# single-spi-interface.net
KiCad netlist of a schematic drawn in EAGLE
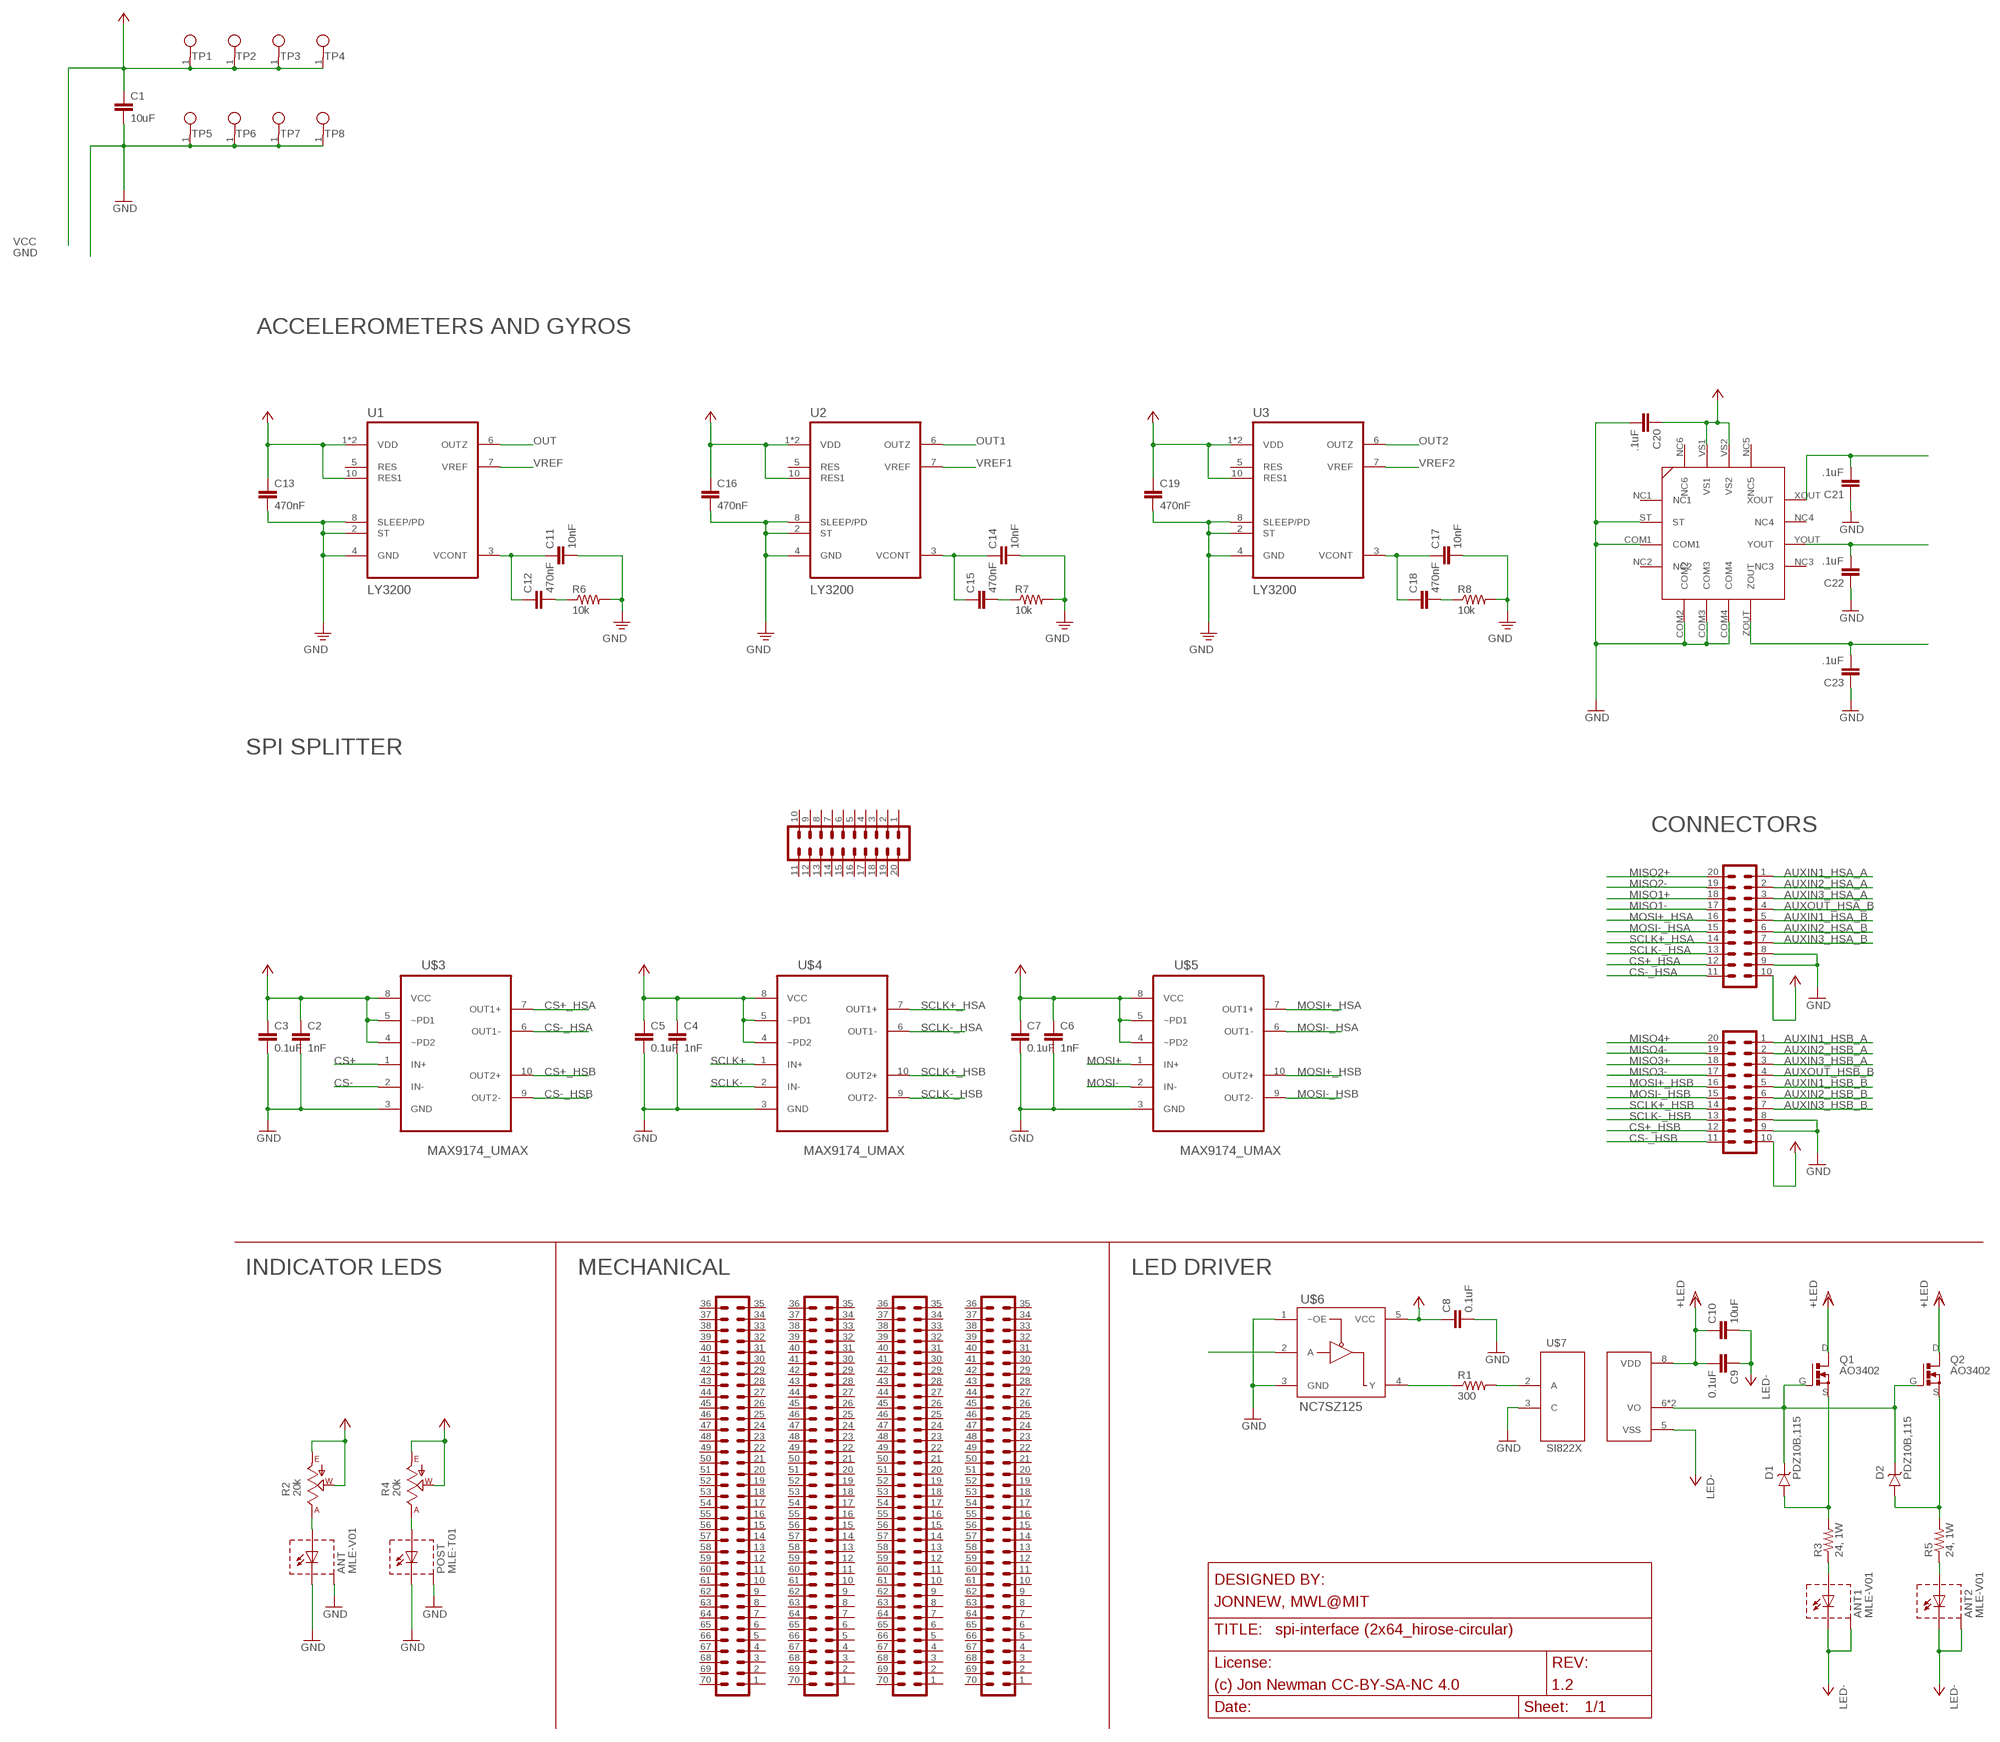
[diagram p0: schematic, sheet 1]

(export (version "E")
  (design (tool "Eeschema 10.0.6"))
  (components
    (comp (ref "ANT")
      (value "MLE-V01")
      (footprint "eagle-import:LED-MLE")
      (libsource (lib "eagle-import") (part "LED_PKG-BODY"))
    )
    (comp (ref "ANT1")
      (value "MLE-V01")
      (footprint "eagle-import:LED-MLE")
      (libsource (lib "eagle-import") (part "LED_PKG-BODY"))
    )
    (comp (ref "ANT2")
      (value "MLE-V01")
      (footprint "eagle-import:LED-MLE")
      (libsource (lib "eagle-import") (part "LED_PKG-BODY"))
    )
    (comp (ref "C1")
      (value "10uF")
      (footprint "eagle-import:0805")
      (fields (field (name "PARTNO") "C2012X5R1Cxxxxxxx"))
      (libsource (lib "eagle-import") (part "C_0805"))
    )
    (comp (ref "C2")
      (value "1nF")
      (footprint "eagle-import:0402")
      (libsource (lib "eagle-import") (part "jonnew_C_0402"))
    )
    (comp (ref "C3")
      (value "0.1uF")
      (footprint "eagle-import:0402")
      (libsource (lib "eagle-import") (part "jonnew_C_0402"))
    )
    (comp (ref "C4")
      (value "1nF")
      (footprint "eagle-import:0402")
      (libsource (lib "eagle-import") (part "jonnew_C_0402"))
    )
    (comp (ref "C5")
      (value "0.1uF")
      (footprint "eagle-import:0402")
      (libsource (lib "eagle-import") (part "jonnew_C_0402"))
    )
    (comp (ref "C6")
      (value "1nF")
      (footprint "eagle-import:0402")
      (libsource (lib "eagle-import") (part "jonnew_C_0402"))
    )
    (comp (ref "C7")
      (value "0.1uF")
      (footprint "eagle-import:0402")
      (libsource (lib "eagle-import") (part "jonnew_C_0402"))
    )
    (comp (ref "C8")
      (value "0.1uF")
      (footprint "eagle-import:0402")
      (libsource (lib "eagle-import") (part "jonnew_C_0402"))
    )
    (comp (ref "C9")
      (value "0.1uF")
      (footprint "eagle-import:0402")
      (libsource (lib "eagle-import") (part "jonnew_C_0402"))
    )
    (comp (ref "C10")
      (value "10uF")
      (footprint "eagle-import:0805")
      (fields (field (name "PARTNO") "C2012X5R1Cxxxxxxx"))
      (libsource (lib "eagle-import") (part "jonnew_C_0805"))
    )
    (comp (ref "C11")
      (value "10nF")
      (footprint "eagle-import:0201")
      (libsource (lib "eagle-import") (part "jonnew_C_0201"))
    )
    (comp (ref "C12")
      (value "470nF")
      (footprint "eagle-import:0201")
      (libsource (lib "eagle-import") (part "jonnew_C_0201"))
    )
    (comp (ref "C13")
      (value "470nF")
      (footprint "eagle-import:0201")
      (libsource (lib "eagle-import") (part "jonnew_C_0201"))
    )
    (comp (ref "C14")
      (value "10nF")
      (footprint "eagle-import:0201")
      (libsource (lib "eagle-import") (part "jonnew_C_0201"))
    )
    (comp (ref "C15")
      (value "470nF")
      (footprint "eagle-import:0201")
      (libsource (lib "eagle-import") (part "jonnew_C_0201"))
    )
    (comp (ref "C16")
      (value "470nF")
      (footprint "eagle-import:0201")
      (libsource (lib "eagle-import") (part "jonnew_C_0201"))
    )
    (comp (ref "C17")
      (value "10nF")
      (footprint "eagle-import:0201")
      (libsource (lib "eagle-import") (part "jonnew_C_0201"))
    )
    (comp (ref "C18")
      (value "470nF")
      (footprint "eagle-import:0201")
      (libsource (lib "eagle-import") (part "jonnew_C_0201"))
    )
    (comp (ref "C19")
      (value "470nF")
      (footprint "eagle-import:0201")
      (libsource (lib "eagle-import") (part "jonnew_C_0201"))
    )
    (comp (ref "C20")
      (value ".1uF")
      (footprint "eagle-import:0402")
      (libsource (lib "eagle-import") (part "C_0402"))
    )
    (comp (ref "C21")
      (value ".1uF")
      (footprint "eagle-import:0201")
      (libsource (lib "eagle-import") (part "jonnew_C_0201"))
    )
    (comp (ref "C22")
      (value ".1uF")
      (footprint "eagle-import:0201")
      (libsource (lib "eagle-import") (part "jonnew_C_0201"))
    )
    (comp (ref "C23")
      (value ".1uF")
      (footprint "eagle-import:0201")
      (libsource (lib "eagle-import") (part "jonnew_C_0201"))
    )
    (comp (ref "D1")
      (value "PDZ10B,115")
      (footprint "eagle-import:SOD-323")
      (libsource (lib "eagle-import") (part "Z-DIODE_SOD-323"))
    )
    (comp (ref "D2")
      (value "PDZ10B,115")
      (footprint "eagle-import:SOD-323")
      (libsource (lib "eagle-import") (part "Z-DIODE_SOD-323"))
    )
    (comp (ref "DIO_E1B")
      (value "PINHD-2X10_DF40-20REC")
      (footprint "eagle-import:DF40-20REC")
      (libsource (lib "eagle-import") (part "PINHD-2X10_DF40-20REC"))
    )
    (comp (ref "DIO_E1B1")
      (value "PINHD-2X10_DF40-20REC")
      (footprint "eagle-import:DF40-20REC")
      (libsource (lib "eagle-import") (part "PINHD-2X10_DF40-20REC"))
    )
    (comp (ref "MECH_E0B")
      (value "PINHD-2X35_DF40REC")
      (footprint "eagle-import:DF40-70REC")
      (libsource (lib "eagle-import") (part "PINHD-2X35_DF40REC"))
    )
    (comp (ref "MECH_N0B")
      (value "PINHD-2X35_DF40REC")
      (footprint "eagle-import:DF40-70REC")
      (libsource (lib "eagle-import") (part "PINHD-2X35_DF40REC"))
    )
    (comp (ref "MECH_S0B")
      (value "PINHD-2X35_DF40REC")
      (footprint "eagle-import:DF40-70REC")
      (libsource (lib "eagle-import") (part "PINHD-2X35_DF40REC"))
    )
    (comp (ref "MECH_W0B")
      (value "PINHD-2X35_DF40REC")
      (footprint "eagle-import:DF40-70REC")
      (libsource (lib "eagle-import") (part "PINHD-2X35_DF40REC"))
    )
    (comp (ref "POST")
      (value "MLE-T01")
      (footprint "eagle-import:LED-MLE")
      (libsource (lib "eagle-import") (part "LED_PKG-BODY"))
    )
    (comp (ref "Q1")
      (value "AO3402")
      (footprint "eagle-import:SOT23-GSD")
      (libsource (lib "eagle-import") (part "N-MOSFET_SOT23-GSD"))
    )
    (comp (ref "Q2")
      (value "AO3402")
      (footprint "eagle-import:SOT23-GSD")
      (libsource (lib "eagle-import") (part "N-MOSFET_SOT23-GSD"))
    )
    (comp (ref "R1")
      (value "300")
      (footprint "eagle-import:0402")
      (libsource (lib "eagle-import") (part "R_0402"))
    )
    (comp (ref "R2")
      (value "20k")
      (footprint "eagle-import:SM-42_43W")
      (libsource (lib "eagle-import") (part "TRIM_US-SM-42/43W"))
    )
    (comp (ref "R3")
      (value "24, 1W")
      (footprint "eagle-import:0402")
      (libsource (lib "eagle-import") (part "R_0402"))
    )
    (comp (ref "R4")
      (value "20k")
      (footprint "eagle-import:SM-42_43W")
      (libsource (lib "eagle-import") (part "TRIM_US-SM-42/43W"))
    )
    (comp (ref "R5")
      (value "24, 1W")
      (footprint "eagle-import:0402")
      (libsource (lib "eagle-import") (part "R_0402"))
    )
    (comp (ref "R6")
      (value "10k")
      (footprint "eagle-import:0201")
      (libsource (lib "eagle-import") (part "R_0201"))
    )
    (comp (ref "R7")
      (value "10k")
      (footprint "eagle-import:0201")
      (libsource (lib "eagle-import") (part "R_0201"))
    )
    (comp (ref "R8")
      (value "10k")
      (footprint "eagle-import:0201")
      (libsource (lib "eagle-import") (part "R_0201"))
    )
    (comp (ref "TP1")
      (value "TESTPOINT_SMALL")
      (footprint "eagle-import:TESTPOINT_SMALL")
      (libsource (lib "eagle-import") (part "TESTPOINT_SMALL"))
    )
    (comp (ref "TP2")
      (value "TESTPOINT_SMALL")
      (footprint "eagle-import:TESTPOINT_SMALL")
      (libsource (lib "eagle-import") (part "TESTPOINT_SMALL"))
    )
    (comp (ref "TP3")
      (value "TESTPOINT_SMALL")
      (footprint "eagle-import:TESTPOINT_SMALL")
      (libsource (lib "eagle-import") (part "TESTPOINT_SMALL"))
    )
    (comp (ref "TP4")
      (value "TESTPOINT_SMALL")
      (footprint "eagle-import:TESTPOINT_SMALL")
      (libsource (lib "eagle-import") (part "TESTPOINT_SMALL"))
    )
    (comp (ref "TP5")
      (value "TESTPOINT_SMALL")
      (footprint "eagle-import:TESTPOINT_SMALL")
      (libsource (lib "eagle-import") (part "TESTPOINT_SMALL"))
    )
    (comp (ref "TP6")
      (value "TESTPOINT_SMALL")
      (footprint "eagle-import:TESTPOINT_SMALL")
      (libsource (lib "eagle-import") (part "TESTPOINT_SMALL"))
    )
    (comp (ref "TP7")
      (value "TESTPOINT_SMALL")
      (footprint "eagle-import:TESTPOINT_SMALL")
      (libsource (lib "eagle-import") (part "TESTPOINT_SMALL"))
    )
    (comp (ref "TP8")
      (value "TESTPOINT_SMALL")
      (footprint "eagle-import:TESTPOINT_SMALL")
      (libsource (lib "eagle-import") (part "TESTPOINT_SMALL"))
    )
    (comp (ref "U$2")
      (value "PINHD-2X10_T1M")
      (footprint "eagle-import:T1M-10-T-DV")
      (libsource (lib "eagle-import") (part "PINHD-2X10_T1M"))
    )
    (comp (ref "U$3")
      (value "MAX9174_UMAX")
      (footprint "eagle-import:10-UMAX")
      (libsource (lib "eagle-import") (part "MAX9174_UMAX"))
    )
    (comp (ref "U$4")
      (value "MAX9174_UMAX")
      (footprint "eagle-import:10-UMAX")
      (libsource (lib "eagle-import") (part "MAX9174_UMAX"))
    )
    (comp (ref "U$5")
      (value "MAX9174_UMAX")
      (footprint "eagle-import:10-UMAX")
      (libsource (lib "eagle-import") (part "MAX9174_UMAX"))
    )
    (comp (ref "U$6")
      (value "NC7SZ125")
      (footprint "eagle-import:SOT-23-5")
      (libsource (lib "eagle-import") (part "NC7SZ125"))
    )
    (comp (ref "U$7")
      (value "SI822X")
      (footprint "eagle-import:SOIC127P500X400-8N")
      (libsource (lib "eagle-import") (part "SI822X"))
    )
    (comp (ref "U1")
      (value "LY3200")
      (footprint "eagle-import:LGA-10-COMPACT")
      (libsource (lib "eagle-import") (part "LY3200ALH_LGA-10-COMPACT"))
    )
    (comp (ref "U2")
      (value "LY3200")
      (footprint "eagle-import:LGA-10-COMPACT")
      (libsource (lib "eagle-import") (part "LY3200ALH_LGA-10-COMPACT"))
    )
    (comp (ref "U3")
      (value "LY3200")
      (footprint "eagle-import:LGA-10-COMPACT")
      (libsource (lib "eagle-import") (part "LY3200ALH_LGA-10-COMPACT"))
    )
    (comp (ref "U4")
      (value "ADXL335")
      (footprint "eagle-import:ADXL335")
      (libsource (lib "eagle-import") (part "ADXL335"))
    )
  )
  (nets
    (net (code "1") (name "+LED") (class "Default")
      (node (ref "C10") (pin "1") (pinfunction "1_1") (pintype "passive"))
      (node (ref "C9") (pin "2") (pinfunction "2_2") (pintype "passive"))
      (node (ref "Q1") (pin "D") (pinfunction "D_D") (pintype "bidirectional"))
      (node (ref "Q2") (pin "D") (pinfunction "D_D") (pintype "bidirectional"))
      (node (ref "U$7") (pin "8") (pinfunction "VDD_8") (pintype "power_in"))
    )
    (net (code "2") (name "/AUXIN1_HSA_A") (class "Default")
      (node (ref "DIO_E1B") (pin "1") (pinfunction "1_1") (pintype "bidirectional"))
    )
    (net (code "3") (name "/AUXIN1_HSA_B") (class "Default")
      (node (ref "DIO_E1B") (pin "5") (pinfunction "5_5") (pintype "bidirectional"))
    )
    (net (code "4") (name "/AUXIN1_HSB_A") (class "Default")
      (node (ref "DIO_E1B1") (pin "1") (pinfunction "1_1") (pintype "bidirectional"))
    )
    (net (code "5") (name "/AUXIN1_HSB_B") (class "Default")
      (node (ref "DIO_E1B1") (pin "5") (pinfunction "5_5") (pintype "bidirectional"))
    )
    (net (code "6") (name "/AUXIN2_HSA_A") (class "Default")
      (node (ref "DIO_E1B") (pin "2") (pinfunction "2_2") (pintype "bidirectional"))
    )
    (net (code "7") (name "/AUXIN2_HSA_B") (class "Default")
      (node (ref "DIO_E1B") (pin "6") (pinfunction "6_6") (pintype "bidirectional"))
    )
    (net (code "8") (name "/AUXIN2_HSB_A") (class "Default")
      (node (ref "DIO_E1B1") (pin "2") (pinfunction "2_2") (pintype "bidirectional"))
    )
    (net (code "9") (name "/AUXIN2_HSB_B") (class "Default")
      (node (ref "DIO_E1B1") (pin "6") (pinfunction "6_6") (pintype "bidirectional"))
    )
    (net (code "10") (name "/AUXIN3_HSA_A") (class "Default")
      (node (ref "DIO_E1B") (pin "3") (pinfunction "3_3") (pintype "bidirectional"))
    )
    (net (code "11") (name "/AUXIN3_HSA_B") (class "Default")
      (node (ref "DIO_E1B") (pin "7") (pinfunction "7_7") (pintype "bidirectional"))
    )
    (net (code "12") (name "/AUXIN3_HSB_A") (class "Default")
      (node (ref "DIO_E1B1") (pin "3") (pinfunction "3_3") (pintype "bidirectional"))
    )
    (net (code "13") (name "/AUXIN3_HSB_B") (class "Default")
      (node (ref "DIO_E1B1") (pin "7") (pinfunction "7_7") (pintype "bidirectional"))
    )
    (net (code "14") (name "/AUXOUT_HSA_B") (class "Default")
      (node (ref "DIO_E1B") (pin "4") (pinfunction "4_4") (pintype "bidirectional"))
    )
    (net (code "15") (name "/AUXOUT_HSB_B") (class "Default")
      (node (ref "DIO_E1B1") (pin "4") (pinfunction "4_4") (pintype "bidirectional"))
    )
    (net (code "16") (name "/CS+") (class "Default")
      (node (ref "U$3") (pin "1") (pinfunction "IN+_1") (pintype "input"))
    )
    (net (code "17") (name "/CS+_HSA") (class "Default")
      (node (ref "DIO_E1B") (pin "12") (pinfunction "12_12") (pintype "bidirectional"))
      (node (ref "U$3") (pin "7") (pinfunction "OUT1+_7") (pintype "output"))
    )
    (net (code "18") (name "/CS+_HSB") (class "Default")
      (node (ref "DIO_E1B1") (pin "12") (pinfunction "12_12") (pintype "bidirectional"))
      (node (ref "U$3") (pin "10") (pinfunction "OUT2+_10") (pintype "output"))
    )
    (net (code "19") (name "/CS-") (class "Default")
      (node (ref "U$3") (pin "2") (pinfunction "IN-_2") (pintype "input"))
    )
    (net (code "20") (name "/CS-_HSA") (class "Default")
      (node (ref "DIO_E1B") (pin "11") (pinfunction "11_11") (pintype "bidirectional"))
      (node (ref "U$3") (pin "6") (pinfunction "OUT1-_6") (pintype "output"))
    )
    (net (code "21") (name "/CS-_HSB") (class "Default")
      (node (ref "DIO_E1B1") (pin "11") (pinfunction "11_11") (pintype "bidirectional"))
      (node (ref "U$3") (pin "9") (pinfunction "OUT2-_9") (pintype "output"))
    )
    (net (code "22") (name "/MISO1+") (class "Default")
      (node (ref "DIO_E1B") (pin "18") (pinfunction "18_18") (pintype "bidirectional"))
    )
    (net (code "23") (name "/MISO1-") (class "Default")
      (node (ref "DIO_E1B") (pin "17") (pinfunction "17_17") (pintype "bidirectional"))
    )
    (net (code "24") (name "/MISO2+") (class "Default")
      (node (ref "DIO_E1B") (pin "20") (pinfunction "20_20") (pintype "bidirectional"))
    )
    (net (code "25") (name "/MISO2-") (class "Default")
      (node (ref "DIO_E1B") (pin "19") (pinfunction "19_19") (pintype "bidirectional"))
    )
    (net (code "26") (name "/MISO3+") (class "Default")
      (node (ref "DIO_E1B1") (pin "18") (pinfunction "18_18") (pintype "bidirectional"))
    )
    (net (code "27") (name "/MISO3-") (class "Default")
      (node (ref "DIO_E1B1") (pin "17") (pinfunction "17_17") (pintype "bidirectional"))
    )
    (net (code "28") (name "/MISO4+") (class "Default")
      (node (ref "DIO_E1B1") (pin "20") (pinfunction "20_20") (pintype "bidirectional"))
    )
    (net (code "29") (name "/MISO4-") (class "Default")
      (node (ref "DIO_E1B1") (pin "19") (pinfunction "19_19") (pintype "bidirectional"))
    )
    (net (code "30") (name "/MOSI+") (class "Default")
      (node (ref "U$5") (pin "1") (pinfunction "IN+_1") (pintype "input"))
    )
    (net (code "31") (name "/MOSI+_HSA") (class "Default")
      (node (ref "DIO_E1B") (pin "16") (pinfunction "16_16") (pintype "bidirectional"))
      (node (ref "U$5") (pin "7") (pinfunction "OUT1+_7") (pintype "output"))
    )
    (net (code "32") (name "/MOSI+_HSB") (class "Default")
      (node (ref "DIO_E1B1") (pin "16") (pinfunction "16_16") (pintype "bidirectional"))
      (node (ref "U$5") (pin "10") (pinfunction "OUT2+_10") (pintype "output"))
    )
    (net (code "33") (name "/MOSI-") (class "Default")
      (node (ref "U$5") (pin "2") (pinfunction "IN-_2") (pintype "input"))
    )
    (net (code "34") (name "/MOSI-_HSA") (class "Default")
      (node (ref "DIO_E1B") (pin "15") (pinfunction "15_15") (pintype "bidirectional"))
      (node (ref "U$5") (pin "6") (pinfunction "OUT1-_6") (pintype "output"))
    )
    (net (code "35") (name "/MOSI-_HSB") (class "Default")
      (node (ref "DIO_E1B1") (pin "15") (pinfunction "15_15") (pintype "bidirectional"))
      (node (ref "U$5") (pin "9") (pinfunction "OUT2-_9") (pintype "output"))
    )
    (net (code "36") (name "/OUT") (class "Default")
      (node (ref "U1") (pin "6") (pinfunction "OUTZ_6") (pintype "output"))
    )
    (net (code "37") (name "/OUT1") (class "Default")
      (node (ref "U2") (pin "6") (pinfunction "OUTZ_6") (pintype "output"))
    )
    (net (code "38") (name "/OUT2") (class "Default")
      (node (ref "U3") (pin "6") (pinfunction "OUTZ_6") (pintype "output"))
    )
    (net (code "39") (name "/SCLK+") (class "Default")
      (node (ref "U$4") (pin "1") (pinfunction "IN+_1") (pintype "input"))
    )
    (net (code "40") (name "/SCLK+_HSA") (class "Default")
      (node (ref "DIO_E1B") (pin "14") (pinfunction "14_14") (pintype "bidirectional"))
      (node (ref "U$4") (pin "7") (pinfunction "OUT1+_7") (pintype "output"))
    )
    (net (code "41") (name "/SCLK+_HSB") (class "Default")
      (node (ref "DIO_E1B1") (pin "14") (pinfunction "14_14") (pintype "bidirectional"))
      (node (ref "U$4") (pin "10") (pinfunction "OUT2+_10") (pintype "output"))
    )
    (net (code "42") (name "/SCLK-") (class "Default")
      (node (ref "U$4") (pin "2") (pinfunction "IN-_2") (pintype "input"))
    )
    (net (code "43") (name "/SCLK-_HSA") (class "Default")
      (node (ref "DIO_E1B") (pin "13") (pinfunction "13_13") (pintype "bidirectional"))
      (node (ref "U$4") (pin "6") (pinfunction "OUT1-_6") (pintype "output"))
    )
    (net (code "44") (name "/SCLK-_HSB") (class "Default")
      (node (ref "DIO_E1B1") (pin "13") (pinfunction "13_13") (pintype "bidirectional"))
      (node (ref "U$4") (pin "9") (pinfunction "OUT2-_9") (pintype "output"))
    )
    (net (code "45") (name "/VREF") (class "Default")
      (node (ref "U1") (pin "7") (pinfunction "VREF_7") (pintype "output"))
    )
    (net (code "46") (name "/VREF1") (class "Default")
      (node (ref "U2") (pin "7") (pinfunction "VREF_7") (pintype "output"))
    )
    (net (code "47") (name "/VREF2") (class "Default")
      (node (ref "U3") (pin "7") (pinfunction "VREF_7") (pintype "output"))
    )
    (net (code "48") (name "GND") (class "Default")
      (node (ref "ANT") (pin "C1") (pinfunction "C_C1") (pintype "passive"))
      (node (ref "ANT") (pin "C2") (pinfunction "C_C2") (pintype "passive"))
      (node (ref "ANT") (pin "HS") (pinfunction "BODY_HS") (pintype "passive"))
      (node (ref "C1") (pin "2") (pinfunction "2_2") (pintype "passive"))
      (node (ref "C11") (pin "2") (pinfunction "2_2") (pintype "passive"))
      (node (ref "C13") (pin "2") (pinfunction "2_2") (pintype "passive"))
      (node (ref "C14") (pin "2") (pinfunction "2_2") (pintype "passive"))
      (node (ref "C16") (pin "2") (pinfunction "2_2") (pintype "passive"))
      (node (ref "C17") (pin "2") (pinfunction "2_2") (pintype "passive"))
      (node (ref "C19") (pin "2") (pinfunction "2_2") (pintype "passive"))
      (node (ref "C2") (pin "2") (pinfunction "2_2") (pintype "passive"))
      (node (ref "C20") (pin "2") (pinfunction "2_2") (pintype "passive"))
      (node (ref "C21") (pin "1") (pinfunction "1_1") (pintype "passive"))
      (node (ref "C22") (pin "1") (pinfunction "1_1") (pintype "passive"))
      (node (ref "C23") (pin "1") (pinfunction "1_1") (pintype "passive"))
      (node (ref "C3") (pin "2") (pinfunction "2_2") (pintype "passive"))
      (node (ref "C4") (pin "2") (pinfunction "2_2") (pintype "passive"))
      (node (ref "C5") (pin "2") (pinfunction "2_2") (pintype "passive"))
      (node (ref "C6") (pin "2") (pinfunction "2_2") (pintype "passive"))
      (node (ref "C7") (pin "2") (pinfunction "2_2") (pintype "passive"))
      (node (ref "C8") (pin "2") (pinfunction "2_2") (pintype "passive"))
      (node (ref "DIO_E1B") (pin "8") (pinfunction "8_8") (pintype "bidirectional"))
      (node (ref "DIO_E1B") (pin "9") (pinfunction "9_9") (pintype "bidirectional"))
      (node (ref "DIO_E1B1") (pin "8") (pinfunction "8_8") (pintype "bidirectional"))
      (node (ref "DIO_E1B1") (pin "9") (pinfunction "9_9") (pintype "bidirectional"))
      (node (ref "POST") (pin "C1") (pinfunction "C_C1") (pintype "passive"))
      (node (ref "POST") (pin "C2") (pinfunction "C_C2") (pintype "passive"))
      (node (ref "POST") (pin "HS") (pinfunction "BODY_HS") (pintype "passive"))
      (node (ref "R6") (pin "2") (pinfunction "2_2") (pintype "passive"))
      (node (ref "R7") (pin "2") (pinfunction "2_2") (pintype "passive"))
      (node (ref "R8") (pin "2") (pinfunction "2_2") (pintype "passive"))
      (node (ref "TP5") (pin "1") (pinfunction "1_1") (pintype "passive"))
      (node (ref "TP6") (pin "1") (pinfunction "1_1") (pintype "passive"))
      (node (ref "TP7") (pin "1") (pinfunction "1_1") (pintype "passive"))
      (node (ref "TP8") (pin "1") (pinfunction "1_1") (pintype "passive"))
      (node (ref "U$3") (pin "3") (pinfunction "GND_3") (pintype "power_in"))
      (node (ref "U$4") (pin "3") (pinfunction "GND_3") (pintype "power_in"))
      (node (ref "U$5") (pin "3") (pinfunction "GND_3") (pintype "power_in"))
      (node (ref "U$6") (pin "1") (pinfunction "~{OE}_1") (pintype "input"))
      (node (ref "U$6") (pin "3") (pinfunction "GND_3") (pintype "power_in"))
      (node (ref "U$7") (pin "3") (pinfunction "C_3") (pintype "bidirectional"))
      (node (ref "U1") (pin "2") (pinfunction "ST_2") (pintype "bidirectional"))
      (node (ref "U1") (pin "4") (pinfunction "GND_4") (pintype "power_in"))
      (node (ref "U1") (pin "8") (pinfunction "SLEEP/PD_8") (pintype "bidirectional"))
      (node (ref "U2") (pin "2") (pinfunction "ST_2") (pintype "bidirectional"))
      (node (ref "U2") (pin "4") (pinfunction "GND_4") (pintype "power_in"))
      (node (ref "U2") (pin "8") (pinfunction "SLEEP/PD_8") (pintype "bidirectional"))
      (node (ref "U3") (pin "2") (pinfunction "ST_2") (pintype "bidirectional"))
      (node (ref "U3") (pin "4") (pinfunction "GND_4") (pintype "power_in"))
      (node (ref "U3") (pin "8") (pinfunction "SLEEP/PD_8") (pintype "bidirectional"))
      (node (ref "U4") (pin "COM1") (pinfunction "COM1_COM1") (pintype "bidirectional"))
      (node (ref "U4") (pin "COM2") (pinfunction "COM2_COM2") (pintype "bidirectional"))
      (node (ref "U4") (pin "COM3") (pinfunction "COM3_COM3") (pintype "bidirectional"))
      (node (ref "U4") (pin "COM4") (pinfunction "COM4_COM4") (pintype "bidirectional"))
      (node (ref "U4") (pin "ST") (pinfunction "ST_ST") (pintype "bidirectional"))
    )
    (net (code "49") (name "LED-") (class "Default")
      (node (ref "ANT1") (pin "C1") (pinfunction "C_C1") (pintype "passive"))
      (node (ref "ANT1") (pin "C2") (pinfunction "C_C2") (pintype "passive"))
      (node (ref "ANT1") (pin "HS") (pinfunction "BODY_HS") (pintype "passive"))
      (node (ref "ANT2") (pin "C1") (pinfunction "C_C1") (pintype "passive"))
      (node (ref "ANT2") (pin "C2") (pinfunction "C_C2") (pintype "passive"))
      (node (ref "ANT2") (pin "HS") (pinfunction "BODY_HS") (pintype "passive"))
      (node (ref "C10") (pin "2") (pinfunction "2_2") (pintype "passive"))
      (node (ref "C9") (pin "1") (pinfunction "1_1") (pintype "passive"))
      (node (ref "U$7") (pin "5") (pinfunction "VSS_5") (pintype "power_in"))
    )
    (net (code "50") (name "Net-(ANT1-A-PadA1)") (class "Default")
      (node (ref "ANT1") (pin "A1") (pinfunction "A_A1") (pintype "passive"))
      (node (ref "ANT1") (pin "A2") (pinfunction "A_A2") (pintype "passive"))
      (node (ref "R3") (pin "1") (pinfunction "1_1") (pintype "passive"))
    )
    (net (code "51") (name "Net-(ANT2-A-PadA1)") (class "Default")
      (node (ref "ANT2") (pin "A1") (pinfunction "A_A1") (pintype "passive"))
      (node (ref "ANT2") (pin "A2") (pinfunction "A_A2") (pintype "passive"))
      (node (ref "R5") (pin "1") (pinfunction "1_1") (pintype "passive"))
    )
    (net (code "52") (name "Net-(C12-Pad2)") (class "Default")
      (node (ref "C12") (pin "2") (pinfunction "2_2") (pintype "passive"))
      (node (ref "R6") (pin "1") (pinfunction "1_1") (pintype "passive"))
    )
    (net (code "53") (name "Net-(C15-Pad2)") (class "Default")
      (node (ref "C15") (pin "2") (pinfunction "2_2") (pintype "passive"))
      (node (ref "R7") (pin "1") (pinfunction "1_1") (pintype "passive"))
    )
    (net (code "54") (name "Net-(C18-Pad2)") (class "Default")
      (node (ref "C18") (pin "2") (pinfunction "2_2") (pintype "passive"))
      (node (ref "R8") (pin "1") (pinfunction "1_1") (pintype "passive"))
    )
    (net (code "55") (name "Net-(C21-Pad2)") (class "Default")
      (node (ref "C21") (pin "2") (pinfunction "2_2") (pintype "passive"))
      (node (ref "U4") (pin "XOUT") (pinfunction "XOUT_XOUT") (pintype "bidirectional"))
    )
    (net (code "56") (name "Net-(C22-Pad2)") (class "Default")
      (node (ref "C22") (pin "2") (pinfunction "2_2") (pintype "passive"))
      (node (ref "U4") (pin "YOUT") (pinfunction "YOUT_YOUT") (pintype "bidirectional"))
    )
    (net (code "57") (name "Net-(C23-Pad2)") (class "Default")
      (node (ref "C23") (pin "2") (pinfunction "2_2") (pintype "passive"))
      (node (ref "U4") (pin "ZOUT") (pinfunction "ZOUT_ZOUT") (pintype "bidirectional"))
    )
    (net (code "58") (name "Net-(D1-PadA)") (class "Default")
      (node (ref "D1") (pin "A") (pinfunction "A_A") (pintype "passive"))
      (node (ref "Q1") (pin "S") (pinfunction "S_S") (pintype "bidirectional"))
      (node (ref "R3") (pin "2") (pinfunction "2_2") (pintype "passive"))
    )
    (net (code "59") (name "Net-(D1-PadC)") (class "Default")
      (node (ref "D1") (pin "C") (pinfunction "C_C") (pintype "passive"))
      (node (ref "D2") (pin "C") (pinfunction "C_C") (pintype "passive"))
      (node (ref "Q1") (pin "G") (pinfunction "G_G") (pintype "bidirectional"))
      (node (ref "Q2") (pin "G") (pinfunction "G_G") (pintype "bidirectional"))
      (node (ref "U$7") (pin "6") (pinfunction "VO_6") (pintype "bidirectional"))
      (node (ref "U$7") (pin "7") (pinfunction "VO_7") (pintype "bidirectional"))
    )
    (net (code "60") (name "Net-(D2-PadA)") (class "Default")
      (node (ref "D2") (pin "A") (pinfunction "A_A") (pintype "passive"))
      (node (ref "Q2") (pin "S") (pinfunction "S_S") (pintype "bidirectional"))
      (node (ref "R5") (pin "2") (pinfunction "2_2") (pintype "passive"))
    )
    (net (code "61") (name "Net-(R2-A)") (class "Default")
      (node (ref "ANT") (pin "A1") (pinfunction "A_A1") (pintype "passive"))
      (node (ref "ANT") (pin "A2") (pinfunction "A_A2") (pintype "passive"))
      (node (ref "R2") (pin "1") (pinfunction "A_1") (pintype "passive"))
    )
    (net (code "62") (name "Net-(R4-A)") (class "Default")
      (node (ref "POST") (pin "A1") (pinfunction "A_A1") (pintype "passive"))
      (node (ref "POST") (pin "A2") (pinfunction "A_A2") (pintype "passive"))
      (node (ref "R4") (pin "1") (pinfunction "A_1") (pintype "passive"))
    )
    (net (code "63") (name "Net-(U$6-Y)") (class "Default")
      (node (ref "R1") (pin "1") (pinfunction "1_1") (pintype "passive"))
      (node (ref "U$6") (pin "4") (pinfunction "Y_4") (pintype "output"))
    )
    (net (code "64") (name "Net-(U$7-A)") (class "Default")
      (node (ref "R1") (pin "2") (pinfunction "2_2") (pintype "passive"))
      (node (ref "U$7") (pin "2") (pinfunction "A_2") (pintype "bidirectional"))
    )
    (net (code "65") (name "Net-(U1-VCONT)") (class "Default")
      (node (ref "C11") (pin "1") (pinfunction "1_1") (pintype "passive"))
      (node (ref "C12") (pin "1") (pinfunction "1_1") (pintype "passive"))
      (node (ref "U1") (pin "3") (pinfunction "VCONT_3") (pintype "passive"))
    )
    (net (code "66") (name "Net-(U2-VCONT)") (class "Default")
      (node (ref "C14") (pin "1") (pinfunction "1_1") (pintype "passive"))
      (node (ref "C15") (pin "1") (pinfunction "1_1") (pintype "passive"))
      (node (ref "U2") (pin "3") (pinfunction "VCONT_3") (pintype "passive"))
    )
    (net (code "67") (name "Net-(U3-VCONT)") (class "Default")
      (node (ref "C17") (pin "1") (pinfunction "1_1") (pintype "passive"))
      (node (ref "C18") (pin "1") (pinfunction "1_1") (pintype "passive"))
      (node (ref "U3") (pin "3") (pinfunction "VCONT_3") (pintype "passive"))
    )
    (net (code "68") (name "VCC") (class "Default")
      (node (ref "C1") (pin "1") (pinfunction "1_1") (pintype "passive"))
      (node (ref "C13") (pin "1") (pinfunction "1_1") (pintype "passive"))
      (node (ref "C16") (pin "1") (pinfunction "1_1") (pintype "passive"))
      (node (ref "C19") (pin "1") (pinfunction "1_1") (pintype "passive"))
      (node (ref "C2") (pin "1") (pinfunction "1_1") (pintype "passive"))
      (node (ref "C20") (pin "1") (pinfunction "1_1") (pintype "passive"))
      (node (ref "C3") (pin "1") (pinfunction "1_1") (pintype "passive"))
      (node (ref "C4") (pin "1") (pinfunction "1_1") (pintype "passive"))
      (node (ref "C5") (pin "1") (pinfunction "1_1") (pintype "passive"))
      (node (ref "C6") (pin "1") (pinfunction "1_1") (pintype "passive"))
      (node (ref "C7") (pin "1") (pinfunction "1_1") (pintype "passive"))
      (node (ref "C8") (pin "1") (pinfunction "1_1") (pintype "passive"))
      (node (ref "DIO_E1B") (pin "10") (pinfunction "10_10") (pintype "bidirectional"))
      (node (ref "DIO_E1B1") (pin "10") (pinfunction "10_10") (pintype "bidirectional"))
      (node (ref "R2") (pin "2") (pinfunction "W_2") (pintype "passive"))
      (node (ref "R2") (pin "3") (pinfunction "E_3") (pintype "passive"))
      (node (ref "R4") (pin "2") (pinfunction "W_2") (pintype "passive"))
      (node (ref "R4") (pin "3") (pinfunction "E_3") (pintype "passive"))
      (node (ref "TP1") (pin "1") (pinfunction "1_1") (pintype "passive"))
      (node (ref "TP2") (pin "1") (pinfunction "1_1") (pintype "passive"))
      (node (ref "TP3") (pin "1") (pinfunction "1_1") (pintype "passive"))
      (node (ref "TP4") (pin "1") (pinfunction "1_1") (pintype "passive"))
      (node (ref "U$3") (pin "4") (pinfunction "~{PD2}_4") (pintype "passive"))
      (node (ref "U$3") (pin "5") (pinfunction "~{PD1}_5") (pintype "passive"))
      (node (ref "U$3") (pin "8") (pinfunction "VCC_8") (pintype "power_in"))
      (node (ref "U$4") (pin "4") (pinfunction "~{PD2}_4") (pintype "passive"))
      (node (ref "U$4") (pin "5") (pinfunction "~{PD1}_5") (pintype "passive"))
      (node (ref "U$4") (pin "8") (pinfunction "VCC_8") (pintype "power_in"))
      (node (ref "U$5") (pin "4") (pinfunction "~{PD2}_4") (pintype "passive"))
      (node (ref "U$5") (pin "5") (pinfunction "~{PD1}_5") (pintype "passive"))
      (node (ref "U$5") (pin "8") (pinfunction "VCC_8") (pintype "power_in"))
      (node (ref "U$6") (pin "5") (pinfunction "VCC_5") (pintype "power_in"))
      (node (ref "U1") (pin "1") (pinfunction "VDD_1") (pintype "power_in"))
      (node (ref "U1") (pin "10") (pinfunction "RES1_10") (pintype "passive"))
      (node (ref "U1") (pin "9") (pinfunction "VDD_9") (pintype "power_in"))
      (node (ref "U2") (pin "1") (pinfunction "VDD_1") (pintype "power_in"))
      (node (ref "U2") (pin "10") (pinfunction "RES1_10") (pintype "passive"))
      (node (ref "U2") (pin "9") (pinfunction "VDD_9") (pintype "power_in"))
      (node (ref "U3") (pin "1") (pinfunction "VDD_1") (pintype "power_in"))
      (node (ref "U3") (pin "10") (pinfunction "RES1_10") (pintype "passive"))
      (node (ref "U3") (pin "9") (pinfunction "VDD_9") (pintype "power_in"))
      (node (ref "U4") (pin "VS1") (pinfunction "VS1_VS1") (pintype "bidirectional"))
      (node (ref "U4") (pin "VS2") (pinfunction "VS2_VS2") (pintype "bidirectional"))
    )
    (net (code "69") (name "unconnected-(MECH_E0B-Pad1)") (class "Default")
      (node (ref "MECH_E0B") (pin "1") (pinfunction "1_1") (pintype "bidirectional"))
    )
    (net (code "70") (name "unconnected-(MECH_E0B-Pad2)") (class "Default")
      (node (ref "MECH_E0B") (pin "2") (pinfunction "2_2") (pintype "bidirectional"))
    )
    (net (code "71") (name "unconnected-(MECH_E0B-Pad3)") (class "Default")
      (node (ref "MECH_E0B") (pin "3") (pinfunction "3_3") (pintype "bidirectional"))
    )
    (net (code "72") (name "unconnected-(MECH_E0B-Pad4)") (class "Default")
      (node (ref "MECH_E0B") (pin "4") (pinfunction "4_4") (pintype "bidirectional"))
    )
    (net (code "73") (name "unconnected-(MECH_E0B-Pad5)") (class "Default")
      (node (ref "MECH_E0B") (pin "5") (pinfunction "5_5") (pintype "bidirectional"))
    )
    (net (code "74") (name "unconnected-(MECH_E0B-Pad6)") (class "Default")
      (node (ref "MECH_E0B") (pin "6") (pinfunction "6_6") (pintype "bidirectional"))
    )
    (net (code "75") (name "unconnected-(MECH_E0B-Pad7)") (class "Default")
      (node (ref "MECH_E0B") (pin "7") (pinfunction "7_7") (pintype "bidirectional"))
    )
    (net (code "76") (name "unconnected-(MECH_E0B-Pad8)") (class "Default")
      (node (ref "MECH_E0B") (pin "8") (pinfunction "8_8") (pintype "bidirectional"))
    )
    (net (code "77") (name "unconnected-(MECH_E0B-Pad9)") (class "Default")
      (node (ref "MECH_E0B") (pin "9") (pinfunction "9_9") (pintype "bidirectional"))
    )
    (net (code "78") (name "unconnected-(MECH_E0B-Pad10)") (class "Default")
      (node (ref "MECH_E0B") (pin "10") (pinfunction "10_10") (pintype "bidirectional"))
    )
    (net (code "79") (name "unconnected-(MECH_E0B-Pad11)") (class "Default")
      (node (ref "MECH_E0B") (pin "11") (pinfunction "11_11") (pintype "bidirectional"))
    )
    (net (code "80") (name "unconnected-(MECH_E0B-Pad12)") (class "Default")
      (node (ref "MECH_E0B") (pin "12") (pinfunction "12_12") (pintype "bidirectional"))
    )
    (net (code "81") (name "unconnected-(MECH_E0B-Pad13)") (class "Default")
      (node (ref "MECH_E0B") (pin "13") (pinfunction "13_13") (pintype "bidirectional"))
    )
    (net (code "82") (name "unconnected-(MECH_E0B-Pad14)") (class "Default")
      (node (ref "MECH_E0B") (pin "14") (pinfunction "14_14") (pintype "bidirectional"))
    )
    (net (code "83") (name "unconnected-(MECH_E0B-Pad15)") (class "Default")
      (node (ref "MECH_E0B") (pin "15") (pinfunction "15_15") (pintype "bidirectional"))
    )
    (net (code "84") (name "unconnected-(MECH_E0B-Pad16)") (class "Default")
      (node (ref "MECH_E0B") (pin "16") (pinfunction "16_16") (pintype "bidirectional"))
    )
    (net (code "85") (name "unconnected-(MECH_E0B-Pad17)") (class "Default")
      (node (ref "MECH_E0B") (pin "17") (pinfunction "17_17") (pintype "bidirectional"))
    )
    (net (code "86") (name "unconnected-(MECH_E0B-Pad18)") (class "Default")
      (node (ref "MECH_E0B") (pin "18") (pinfunction "18_18") (pintype "bidirectional"))
    )
    (net (code "87") (name "unconnected-(MECH_E0B-Pad19)") (class "Default")
      (node (ref "MECH_E0B") (pin "19") (pinfunction "19_19") (pintype "bidirectional"))
    )
    (net (code "88") (name "unconnected-(MECH_E0B-Pad20)") (class "Default")
      (node (ref "MECH_E0B") (pin "20") (pinfunction "20_20") (pintype "bidirectional"))
    )
    (net (code "89") (name "unconnected-(MECH_E0B-Pad21)") (class "Default")
      (node (ref "MECH_E0B") (pin "21") (pinfunction "21_21") (pintype "bidirectional"))
    )
    (net (code "90") (name "unconnected-(MECH_E0B-Pad22)") (class "Default")
      (node (ref "MECH_E0B") (pin "22") (pinfunction "22_22") (pintype "bidirectional"))
    )
    (net (code "91") (name "unconnected-(MECH_E0B-Pad23)") (class "Default")
      (node (ref "MECH_E0B") (pin "23") (pinfunction "23_23") (pintype "bidirectional"))
    )
    (net (code "92") (name "unconnected-(MECH_E0B-Pad24)") (class "Default")
      (node (ref "MECH_E0B") (pin "24") (pinfunction "24_24") (pintype "bidirectional"))
    )
    (net (code "93") (name "unconnected-(MECH_E0B-Pad25)") (class "Default")
      (node (ref "MECH_E0B") (pin "25") (pinfunction "25_25") (pintype "bidirectional"))
    )
    (net (code "94") (name "unconnected-(MECH_E0B-Pad26)") (class "Default")
      (node (ref "MECH_E0B") (pin "26") (pinfunction "26_26") (pintype "bidirectional"))
    )
    (net (code "95") (name "unconnected-(MECH_E0B-Pad27)") (class "Default")
      (node (ref "MECH_E0B") (pin "27") (pinfunction "27_27") (pintype "bidirectional"))
    )
    (net (code "96") (name "unconnected-(MECH_E0B-Pad28)") (class "Default")
      (node (ref "MECH_E0B") (pin "28") (pinfunction "28_28") (pintype "bidirectional"))
    )
    (net (code "97") (name "unconnected-(MECH_E0B-Pad29)") (class "Default")
      (node (ref "MECH_E0B") (pin "29") (pinfunction "29_29") (pintype "bidirectional"))
    )
    (net (code "98") (name "unconnected-(MECH_E0B-Pad30)") (class "Default")
      (node (ref "MECH_E0B") (pin "30") (pinfunction "30_30") (pintype "bidirectional"))
    )
    (net (code "99") (name "unconnected-(MECH_E0B-Pad31)") (class "Default")
      (node (ref "MECH_E0B") (pin "31") (pinfunction "31_31") (pintype "bidirectional"))
    )
    (net (code "100") (name "unconnected-(MECH_E0B-Pad32)") (class "Default")
      (node (ref "MECH_E0B") (pin "32") (pinfunction "32_32") (pintype "bidirectional"))
    )
    (net (code "101") (name "unconnected-(MECH_E0B-Pad33)") (class "Default")
      (node (ref "MECH_E0B") (pin "33") (pinfunction "33_33") (pintype "bidirectional"))
    )
    (net (code "102") (name "unconnected-(MECH_E0B-Pad34)") (class "Default")
      (node (ref "MECH_E0B") (pin "34") (pinfunction "34_34") (pintype "bidirectional"))
    )
    (net (code "103") (name "unconnected-(MECH_E0B-Pad35)") (class "Default")
      (node (ref "MECH_E0B") (pin "35") (pinfunction "35_35") (pintype "bidirectional"))
    )
    (net (code "104") (name "unconnected-(MECH_E0B-Pad36)") (class "Default")
      (node (ref "MECH_E0B") (pin "36") (pinfunction "36_36") (pintype "bidirectional"))
    )
    (net (code "105") (name "unconnected-(MECH_E0B-Pad37)") (class "Default")
      (node (ref "MECH_E0B") (pin "37") (pinfunction "37_37") (pintype "bidirectional"))
    )
    (net (code "106") (name "unconnected-(MECH_E0B-Pad38)") (class "Default")
      (node (ref "MECH_E0B") (pin "38") (pinfunction "38_38") (pintype "bidirectional"))
    )
    (net (code "107") (name "unconnected-(MECH_E0B-Pad39)") (class "Default")
      (node (ref "MECH_E0B") (pin "39") (pinfunction "39_39") (pintype "bidirectional"))
    )
    (net (code "108") (name "unconnected-(MECH_E0B-Pad40)") (class "Default")
      (node (ref "MECH_E0B") (pin "40") (pinfunction "40_40") (pintype "bidirectional"))
    )
    (net (code "109") (name "unconnected-(MECH_E0B-Pad41)") (class "Default")
      (node (ref "MECH_E0B") (pin "41") (pinfunction "41_41") (pintype "bidirectional"))
    )
    (net (code "110") (name "unconnected-(MECH_E0B-Pad42)") (class "Default")
      (node (ref "MECH_E0B") (pin "42") (pinfunction "42_42") (pintype "bidirectional"))
    )
    (net (code "111") (name "unconnected-(MECH_E0B-Pad43)") (class "Default")
      (node (ref "MECH_E0B") (pin "43") (pinfunction "43_43") (pintype "bidirectional"))
    )
    (net (code "112") (name "unconnected-(MECH_E0B-Pad44)") (class "Default")
      (node (ref "MECH_E0B") (pin "44") (pinfunction "44_44") (pintype "bidirectional"))
    )
    (net (code "113") (name "unconnected-(MECH_E0B-Pad45)") (class "Default")
      (node (ref "MECH_E0B") (pin "45") (pinfunction "45_45") (pintype "bidirectional"))
    )
    (net (code "114") (name "unconnected-(MECH_E0B-Pad46)") (class "Default")
      (node (ref "MECH_E0B") (pin "46") (pinfunction "46_46") (pintype "bidirectional"))
    )
    (net (code "115") (name "unconnected-(MECH_E0B-Pad47)") (class "Default")
      (node (ref "MECH_E0B") (pin "47") (pinfunction "47_47") (pintype "bidirectional"))
    )
    (net (code "116") (name "unconnected-(MECH_E0B-Pad48)") (class "Default")
      (node (ref "MECH_E0B") (pin "48") (pinfunction "48_48") (pintype "bidirectional"))
    )
    (net (code "117") (name "unconnected-(MECH_E0B-Pad49)") (class "Default")
      (node (ref "MECH_E0B") (pin "49") (pinfunction "49_49") (pintype "bidirectional"))
    )
    (net (code "118") (name "unconnected-(MECH_E0B-Pad50)") (class "Default")
      (node (ref "MECH_E0B") (pin "50") (pinfunction "50_50") (pintype "bidirectional"))
    )
    (net (code "119") (name "unconnected-(MECH_E0B-Pad51)") (class "Default")
      (node (ref "MECH_E0B") (pin "51") (pinfunction "51_51") (pintype "bidirectional"))
    )
    (net (code "120") (name "unconnected-(MECH_E0B-Pad52)") (class "Default")
      (node (ref "MECH_E0B") (pin "52") (pinfunction "52_52") (pintype "bidirectional"))
    )
    (net (code "121") (name "unconnected-(MECH_E0B-Pad53)") (class "Default")
      (node (ref "MECH_E0B") (pin "53") (pinfunction "53_53") (pintype "bidirectional"))
    )
    (net (code "122") (name "unconnected-(MECH_E0B-Pad54)") (class "Default")
      (node (ref "MECH_E0B") (pin "54") (pinfunction "54_54") (pintype "bidirectional"))
    )
    (net (code "123") (name "unconnected-(MECH_E0B-Pad55)") (class "Default")
      (node (ref "MECH_E0B") (pin "55") (pinfunction "55_55") (pintype "bidirectional"))
    )
    (net (code "124") (name "unconnected-(MECH_E0B-Pad56)") (class "Default")
      (node (ref "MECH_E0B") (pin "56") (pinfunction "56_56") (pintype "bidirectional"))
    )
    (net (code "125") (name "unconnected-(MECH_E0B-Pad57)") (class "Default")
      (node (ref "MECH_E0B") (pin "57") (pinfunction "57_57") (pintype "bidirectional"))
    )
    (net (code "126") (name "unconnected-(MECH_E0B-Pad58)") (class "Default")
      (node (ref "MECH_E0B") (pin "58") (pinfunction "58_58") (pintype "bidirectional"))
    )
    (net (code "127") (name "unconnected-(MECH_E0B-Pad59)") (class "Default")
      (node (ref "MECH_E0B") (pin "59") (pinfunction "59_59") (pintype "bidirectional"))
    )
    (net (code "128") (name "unconnected-(MECH_E0B-Pad60)") (class "Default")
      (node (ref "MECH_E0B") (pin "60") (pinfunction "60_60") (pintype "bidirectional"))
    )
    (net (code "129") (name "unconnected-(MECH_E0B-Pad61)") (class "Default")
      (node (ref "MECH_E0B") (pin "61") (pinfunction "61_61") (pintype "bidirectional"))
    )
    (net (code "130") (name "unconnected-(MECH_E0B-Pad62)") (class "Default")
      (node (ref "MECH_E0B") (pin "62") (pinfunction "62_62") (pintype "bidirectional"))
    )
    (net (code "131") (name "unconnected-(MECH_E0B-Pad63)") (class "Default")
      (node (ref "MECH_E0B") (pin "63") (pinfunction "63_63") (pintype "bidirectional"))
    )
    (net (code "132") (name "unconnected-(MECH_E0B-Pad64)") (class "Default")
      (node (ref "MECH_E0B") (pin "64") (pinfunction "64_64") (pintype "bidirectional"))
    )
    (net (code "133") (name "unconnected-(MECH_E0B-Pad65)") (class "Default")
      (node (ref "MECH_E0B") (pin "65") (pinfunction "65_65") (pintype "bidirectional"))
    )
    (net (code "134") (name "unconnected-(MECH_E0B-Pad66)") (class "Default")
      (node (ref "MECH_E0B") (pin "66") (pinfunction "66_66") (pintype "bidirectional"))
    )
    (net (code "135") (name "unconnected-(MECH_E0B-Pad67)") (class "Default")
      (node (ref "MECH_E0B") (pin "67") (pinfunction "67_67") (pintype "bidirectional"))
    )
    (net (code "136") (name "unconnected-(MECH_E0B-Pad68)") (class "Default")
      (node (ref "MECH_E0B") (pin "68") (pinfunction "68_68") (pintype "bidirectional"))
    )
    (net (code "137") (name "unconnected-(MECH_E0B-Pad69)") (class "Default")
      (node (ref "MECH_E0B") (pin "69") (pinfunction "69_69") (pintype "bidirectional"))
    )
    (net (code "138") (name "unconnected-(MECH_E0B-Pad70)") (class "Default")
      (node (ref "MECH_E0B") (pin "70") (pinfunction "70_70") (pintype "bidirectional"))
    )
    (net (code "139") (name "unconnected-(MECH_N0B-Pad1)") (class "Default")
      (node (ref "MECH_N0B") (pin "1") (pinfunction "1_1") (pintype "bidirectional"))
    )
    (net (code "140") (name "unconnected-(MECH_N0B-Pad2)") (class "Default")
      (node (ref "MECH_N0B") (pin "2") (pinfunction "2_2") (pintype "bidirectional"))
    )
    (net (code "141") (name "unconnected-(MECH_N0B-Pad3)") (class "Default")
      (node (ref "MECH_N0B") (pin "3") (pinfunction "3_3") (pintype "bidirectional"))
    )
    (net (code "142") (name "unconnected-(MECH_N0B-Pad4)") (class "Default")
      (node (ref "MECH_N0B") (pin "4") (pinfunction "4_4") (pintype "bidirectional"))
    )
    (net (code "143") (name "unconnected-(MECH_N0B-Pad5)") (class "Default")
      (node (ref "MECH_N0B") (pin "5") (pinfunction "5_5") (pintype "bidirectional"))
    )
    (net (code "144") (name "unconnected-(MECH_N0B-Pad6)") (class "Default")
      (node (ref "MECH_N0B") (pin "6") (pinfunction "6_6") (pintype "bidirectional"))
    )
    (net (code "145") (name "unconnected-(MECH_N0B-Pad7)") (class "Default")
      (node (ref "MECH_N0B") (pin "7") (pinfunction "7_7") (pintype "bidirectional"))
    )
    (net (code "146") (name "unconnected-(MECH_N0B-Pad8)") (class "Default")
      (node (ref "MECH_N0B") (pin "8") (pinfunction "8_8") (pintype "bidirectional"))
    )
    (net (code "147") (name "unconnected-(MECH_N0B-Pad9)") (class "Default")
      (node (ref "MECH_N0B") (pin "9") (pinfunction "9_9") (pintype "bidirectional"))
    )
    (net (code "148") (name "unconnected-(MECH_N0B-Pad10)") (class "Default")
      (node (ref "MECH_N0B") (pin "10") (pinfunction "10_10") (pintype "bidirectional"))
    )
    (net (code "149") (name "unconnected-(MECH_N0B-Pad11)") (class "Default")
      (node (ref "MECH_N0B") (pin "11") (pinfunction "11_11") (pintype "bidirectional"))
    )
    (net (code "150") (name "unconnected-(MECH_N0B-Pad12)") (class "Default")
      (node (ref "MECH_N0B") (pin "12") (pinfunction "12_12") (pintype "bidirectional"))
    )
    (net (code "151") (name "unconnected-(MECH_N0B-Pad13)") (class "Default")
      (node (ref "MECH_N0B") (pin "13") (pinfunction "13_13") (pintype "bidirectional"))
    )
    (net (code "152") (name "unconnected-(MECH_N0B-Pad14)") (class "Default")
      (node (ref "MECH_N0B") (pin "14") (pinfunction "14_14") (pintype "bidirectional"))
    )
    (net (code "153") (name "unconnected-(MECH_N0B-Pad15)") (class "Default")
      (node (ref "MECH_N0B") (pin "15") (pinfunction "15_15") (pintype "bidirectional"))
    )
    (net (code "154") (name "unconnected-(MECH_N0B-Pad16)") (class "Default")
      (node (ref "MECH_N0B") (pin "16") (pinfunction "16_16") (pintype "bidirectional"))
    )
    (net (code "155") (name "unconnected-(MECH_N0B-Pad17)") (class "Default")
      (node (ref "MECH_N0B") (pin "17") (pinfunction "17_17") (pintype "bidirectional"))
    )
    (net (code "156") (name "unconnected-(MECH_N0B-Pad18)") (class "Default")
      (node (ref "MECH_N0B") (pin "18") (pinfunction "18_18") (pintype "bidirectional"))
    )
    (net (code "157") (name "unconnected-(MECH_N0B-Pad19)") (class "Default")
      (node (ref "MECH_N0B") (pin "19") (pinfunction "19_19") (pintype "bidirectional"))
    )
    (net (code "158") (name "unconnected-(MECH_N0B-Pad20)") (class "Default")
      (node (ref "MECH_N0B") (pin "20") (pinfunction "20_20") (pintype "bidirectional"))
    )
    (net (code "159") (name "unconnected-(MECH_N0B-Pad21)") (class "Default")
      (node (ref "MECH_N0B") (pin "21") (pinfunction "21_21") (pintype "bidirectional"))
    )
    (net (code "160") (name "unconnected-(MECH_N0B-Pad22)") (class "Default")
      (node (ref "MECH_N0B") (pin "22") (pinfunction "22_22") (pintype "bidirectional"))
    )
    (net (code "161") (name "unconnected-(MECH_N0B-Pad23)") (class "Default")
      (node (ref "MECH_N0B") (pin "23") (pinfunction "23_23") (pintype "bidirectional"))
    )
    (net (code "162") (name "unconnected-(MECH_N0B-Pad24)") (class "Default")
      (node (ref "MECH_N0B") (pin "24") (pinfunction "24_24") (pintype "bidirectional"))
    )
    (net (code "163") (name "unconnected-(MECH_N0B-Pad25)") (class "Default")
      (node (ref "MECH_N0B") (pin "25") (pinfunction "25_25") (pintype "bidirectional"))
    )
    (net (code "164") (name "unconnected-(MECH_N0B-Pad26)") (class "Default")
      (node (ref "MECH_N0B") (pin "26") (pinfunction "26_26") (pintype "bidirectional"))
    )
    (net (code "165") (name "unconnected-(MECH_N0B-Pad27)") (class "Default")
      (node (ref "MECH_N0B") (pin "27") (pinfunction "27_27") (pintype "bidirectional"))
    )
    (net (code "166") (name "unconnected-(MECH_N0B-Pad28)") (class "Default")
      (node (ref "MECH_N0B") (pin "28") (pinfunction "28_28") (pintype "bidirectional"))
    )
    (net (code "167") (name "unconnected-(MECH_N0B-Pad29)") (class "Default")
      (node (ref "MECH_N0B") (pin "29") (pinfunction "29_29") (pintype "bidirectional"))
    )
    (net (code "168") (name "unconnected-(MECH_N0B-Pad30)") (class "Default")
      (node (ref "MECH_N0B") (pin "30") (pinfunction "30_30") (pintype "bidirectional"))
    )
    (net (code "169") (name "unconnected-(MECH_N0B-Pad31)") (class "Default")
      (node (ref "MECH_N0B") (pin "31") (pinfunction "31_31") (pintype "bidirectional"))
    )
    (net (code "170") (name "unconnected-(MECH_N0B-Pad32)") (class "Default")
      (node (ref "MECH_N0B") (pin "32") (pinfunction "32_32") (pintype "bidirectional"))
    )
    (net (code "171") (name "unconnected-(MECH_N0B-Pad33)") (class "Default")
      (node (ref "MECH_N0B") (pin "33") (pinfunction "33_33") (pintype "bidirectional"))
    )
    (net (code "172") (name "unconnected-(MECH_N0B-Pad34)") (class "Default")
      (node (ref "MECH_N0B") (pin "34") (pinfunction "34_34") (pintype "bidirectional"))
    )
    (net (code "173") (name "unconnected-(MECH_N0B-Pad35)") (class "Default")
      (node (ref "MECH_N0B") (pin "35") (pinfunction "35_35") (pintype "bidirectional"))
    )
    (net (code "174") (name "unconnected-(MECH_N0B-Pad36)") (class "Default")
      (node (ref "MECH_N0B") (pin "36") (pinfunction "36_36") (pintype "bidirectional"))
    )
    (net (code "175") (name "unconnected-(MECH_N0B-Pad37)") (class "Default")
      (node (ref "MECH_N0B") (pin "37") (pinfunction "37_37") (pintype "bidirectional"))
    )
    (net (code "176") (name "unconnected-(MECH_N0B-Pad38)") (class "Default")
      (node (ref "MECH_N0B") (pin "38") (pinfunction "38_38") (pintype "bidirectional"))
    )
    (net (code "177") (name "unconnected-(MECH_N0B-Pad39)") (class "Default")
      (node (ref "MECH_N0B") (pin "39") (pinfunction "39_39") (pintype "bidirectional"))
    )
    (net (code "178") (name "unconnected-(MECH_N0B-Pad40)") (class "Default")
      (node (ref "MECH_N0B") (pin "40") (pinfunction "40_40") (pintype "bidirectional"))
    )
    (net (code "179") (name "unconnected-(MECH_N0B-Pad41)") (class "Default")
      (node (ref "MECH_N0B") (pin "41") (pinfunction "41_41") (pintype "bidirectional"))
    )
    (net (code "180") (name "unconnected-(MECH_N0B-Pad42)") (class "Default")
      (node (ref "MECH_N0B") (pin "42") (pinfunction "42_42") (pintype "bidirectional"))
    )
    (net (code "181") (name "unconnected-(MECH_N0B-Pad43)") (class "Default")
      (node (ref "MECH_N0B") (pin "43") (pinfunction "43_43") (pintype "bidirectional"))
    )
    (net (code "182") (name "unconnected-(MECH_N0B-Pad44)") (class "Default")
      (node (ref "MECH_N0B") (pin "44") (pinfunction "44_44") (pintype "bidirectional"))
    )
    (net (code "183") (name "unconnected-(MECH_N0B-Pad45)") (class "Default")
      (node (ref "MECH_N0B") (pin "45") (pinfunction "45_45") (pintype "bidirectional"))
    )
    (net (code "184") (name "unconnected-(MECH_N0B-Pad46)") (class "Default")
      (node (ref "MECH_N0B") (pin "46") (pinfunction "46_46") (pintype "bidirectional"))
    )
    (net (code "185") (name "unconnected-(MECH_N0B-Pad47)") (class "Default")
      (node (ref "MECH_N0B") (pin "47") (pinfunction "47_47") (pintype "bidirectional"))
    )
    (net (code "186") (name "unconnected-(MECH_N0B-Pad48)") (class "Default")
      (node (ref "MECH_N0B") (pin "48") (pinfunction "48_48") (pintype "bidirectional"))
    )
    (net (code "187") (name "unconnected-(MECH_N0B-Pad49)") (class "Default")
      (node (ref "MECH_N0B") (pin "49") (pinfunction "49_49") (pintype "bidirectional"))
    )
    (net (code "188") (name "unconnected-(MECH_N0B-Pad50)") (class "Default")
      (node (ref "MECH_N0B") (pin "50") (pinfunction "50_50") (pintype "bidirectional"))
    )
    (net (code "189") (name "unconnected-(MECH_N0B-Pad51)") (class "Default")
      (node (ref "MECH_N0B") (pin "51") (pinfunction "51_51") (pintype "bidirectional"))
    )
    (net (code "190") (name "unconnected-(MECH_N0B-Pad52)") (class "Default")
      (node (ref "MECH_N0B") (pin "52") (pinfunction "52_52") (pintype "bidirectional"))
    )
    (net (code "191") (name "unconnected-(MECH_N0B-Pad53)") (class "Default")
      (node (ref "MECH_N0B") (pin "53") (pinfunction "53_53") (pintype "bidirectional"))
    )
    (net (code "192") (name "unconnected-(MECH_N0B-Pad54)") (class "Default")
      (node (ref "MECH_N0B") (pin "54") (pinfunction "54_54") (pintype "bidirectional"))
    )
    (net (code "193") (name "unconnected-(MECH_N0B-Pad55)") (class "Default")
      (node (ref "MECH_N0B") (pin "55") (pinfunction "55_55") (pintype "bidirectional"))
    )
    (net (code "194") (name "unconnected-(MECH_N0B-Pad56)") (class "Default")
      (node (ref "MECH_N0B") (pin "56") (pinfunction "56_56") (pintype "bidirectional"))
    )
    (net (code "195") (name "unconnected-(MECH_N0B-Pad57)") (class "Default")
      (node (ref "MECH_N0B") (pin "57") (pinfunction "57_57") (pintype "bidirectional"))
    )
    (net (code "196") (name "unconnected-(MECH_N0B-Pad58)") (class "Default")
      (node (ref "MECH_N0B") (pin "58") (pinfunction "58_58") (pintype "bidirectional"))
    )
    (net (code "197") (name "unconnected-(MECH_N0B-Pad59)") (class "Default")
      (node (ref "MECH_N0B") (pin "59") (pinfunction "59_59") (pintype "bidirectional"))
    )
    (net (code "198") (name "unconnected-(MECH_N0B-Pad60)") (class "Default")
      (node (ref "MECH_N0B") (pin "60") (pinfunction "60_60") (pintype "bidirectional"))
    )
    (net (code "199") (name "unconnected-(MECH_N0B-Pad61)") (class "Default")
      (node (ref "MECH_N0B") (pin "61") (pinfunction "61_61") (pintype "bidirectional"))
    )
    (net (code "200") (name "unconnected-(MECH_N0B-Pad62)") (class "Default")
      (node (ref "MECH_N0B") (pin "62") (pinfunction "62_62") (pintype "bidirectional"))
    )
    (net (code "201") (name "unconnected-(MECH_N0B-Pad63)") (class "Default")
      (node (ref "MECH_N0B") (pin "63") (pinfunction "63_63") (pintype "bidirectional"))
    )
    (net (code "202") (name "unconnected-(MECH_N0B-Pad64)") (class "Default")
      (node (ref "MECH_N0B") (pin "64") (pinfunction "64_64") (pintype "bidirectional"))
    )
    (net (code "203") (name "unconnected-(MECH_N0B-Pad65)") (class "Default")
      (node (ref "MECH_N0B") (pin "65") (pinfunction "65_65") (pintype "bidirectional"))
    )
    (net (code "204") (name "unconnected-(MECH_N0B-Pad66)") (class "Default")
      (node (ref "MECH_N0B") (pin "66") (pinfunction "66_66") (pintype "bidirectional"))
    )
    (net (code "205") (name "unconnected-(MECH_N0B-Pad67)") (class "Default")
      (node (ref "MECH_N0B") (pin "67") (pinfunction "67_67") (pintype "bidirectional"))
    )
    (net (code "206") (name "unconnected-(MECH_N0B-Pad68)") (class "Default")
      (node (ref "MECH_N0B") (pin "68") (pinfunction "68_68") (pintype "bidirectional"))
    )
    (net (code "207") (name "unconnected-(MECH_N0B-Pad69)") (class "Default")
      (node (ref "MECH_N0B") (pin "69") (pinfunction "69_69") (pintype "bidirectional"))
    )
    (net (code "208") (name "unconnected-(MECH_N0B-Pad70)") (class "Default")
      (node (ref "MECH_N0B") (pin "70") (pinfunction "70_70") (pintype "bidirectional"))
    )
    (net (code "209") (name "unconnected-(MECH_S0B-Pad1)") (class "Default")
      (node (ref "MECH_S0B") (pin "1") (pinfunction "1_1") (pintype "bidirectional"))
    )
    (net (code "210") (name "unconnected-(MECH_S0B-Pad2)") (class "Default")
      (node (ref "MECH_S0B") (pin "2") (pinfunction "2_2") (pintype "bidirectional"))
    )
    (net (code "211") (name "unconnected-(MECH_S0B-Pad3)") (class "Default")
      (node (ref "MECH_S0B") (pin "3") (pinfunction "3_3") (pintype "bidirectional"))
    )
    (net (code "212") (name "unconnected-(MECH_S0B-Pad4)") (class "Default")
      (node (ref "MECH_S0B") (pin "4") (pinfunction "4_4") (pintype "bidirectional"))
    )
    (net (code "213") (name "unconnected-(MECH_S0B-Pad5)") (class "Default")
      (node (ref "MECH_S0B") (pin "5") (pinfunction "5_5") (pintype "bidirectional"))
    )
    (net (code "214") (name "unconnected-(MECH_S0B-Pad6)") (class "Default")
      (node (ref "MECH_S0B") (pin "6") (pinfunction "6_6") (pintype "bidirectional"))
    )
    (net (code "215") (name "unconnected-(MECH_S0B-Pad7)") (class "Default")
      (node (ref "MECH_S0B") (pin "7") (pinfunction "7_7") (pintype "bidirectional"))
    )
    (net (code "216") (name "unconnected-(MECH_S0B-Pad8)") (class "Default")
      (node (ref "MECH_S0B") (pin "8") (pinfunction "8_8") (pintype "bidirectional"))
    )
    (net (code "217") (name "unconnected-(MECH_S0B-Pad9)") (class "Default")
      (node (ref "MECH_S0B") (pin "9") (pinfunction "9_9") (pintype "bidirectional"))
    )
    (net (code "218") (name "unconnected-(MECH_S0B-Pad10)") (class "Default")
      (node (ref "MECH_S0B") (pin "10") (pinfunction "10_10") (pintype "bidirectional"))
    )
    (net (code "219") (name "unconnected-(MECH_S0B-Pad11)") (class "Default")
      (node (ref "MECH_S0B") (pin "11") (pinfunction "11_11") (pintype "bidirectional"))
    )
    (net (code "220") (name "unconnected-(MECH_S0B-Pad12)") (class "Default")
      (node (ref "MECH_S0B") (pin "12") (pinfunction "12_12") (pintype "bidirectional"))
    )
    (net (code "221") (name "unconnected-(MECH_S0B-Pad13)") (class "Default")
      (node (ref "MECH_S0B") (pin "13") (pinfunction "13_13") (pintype "bidirectional"))
    )
    (net (code "222") (name "unconnected-(MECH_S0B-Pad14)") (class "Default")
      (node (ref "MECH_S0B") (pin "14") (pinfunction "14_14") (pintype "bidirectional"))
    )
    (net (code "223") (name "unconnected-(MECH_S0B-Pad15)") (class "Default")
      (node (ref "MECH_S0B") (pin "15") (pinfunction "15_15") (pintype "bidirectional"))
    )
    (net (code "224") (name "unconnected-(MECH_S0B-Pad16)") (class "Default")
      (node (ref "MECH_S0B") (pin "16") (pinfunction "16_16") (pintype "bidirectional"))
    )
    (net (code "225") (name "unconnected-(MECH_S0B-Pad17)") (class "Default")
      (node (ref "MECH_S0B") (pin "17") (pinfunction "17_17") (pintype "bidirectional"))
    )
    (net (code "226") (name "unconnected-(MECH_S0B-Pad18)") (class "Default")
      (node (ref "MECH_S0B") (pin "18") (pinfunction "18_18") (pintype "bidirectional"))
    )
    (net (code "227") (name "unconnected-(MECH_S0B-Pad19)") (class "Default")
      (node (ref "MECH_S0B") (pin "19") (pinfunction "19_19") (pintype "bidirectional"))
    )
    (net (code "228") (name "unconnected-(MECH_S0B-Pad20)") (class "Default")
      (node (ref "MECH_S0B") (pin "20") (pinfunction "20_20") (pintype "bidirectional"))
    )
    (net (code "229") (name "unconnected-(MECH_S0B-Pad21)") (class "Default")
      (node (ref "MECH_S0B") (pin "21") (pinfunction "21_21") (pintype "bidirectional"))
    )
    (net (code "230") (name "unconnected-(MECH_S0B-Pad22)") (class "Default")
      (node (ref "MECH_S0B") (pin "22") (pinfunction "22_22") (pintype "bidirectional"))
    )
    (net (code "231") (name "unconnected-(MECH_S0B-Pad23)") (class "Default")
      (node (ref "MECH_S0B") (pin "23") (pinfunction "23_23") (pintype "bidirectional"))
    )
    (net (code "232") (name "unconnected-(MECH_S0B-Pad24)") (class "Default")
      (node (ref "MECH_S0B") (pin "24") (pinfunction "24_24") (pintype "bidirectional"))
    )
    (net (code "233") (name "unconnected-(MECH_S0B-Pad25)") (class "Default")
      (node (ref "MECH_S0B") (pin "25") (pinfunction "25_25") (pintype "bidirectional"))
    )
    (net (code "234") (name "unconnected-(MECH_S0B-Pad26)") (class "Default")
      (node (ref "MECH_S0B") (pin "26") (pinfunction "26_26") (pintype "bidirectional"))
    )
    (net (code "235") (name "unconnected-(MECH_S0B-Pad27)") (class "Default")
      (node (ref "MECH_S0B") (pin "27") (pinfunction "27_27") (pintype "bidirectional"))
    )
    (net (code "236") (name "unconnected-(MECH_S0B-Pad28)") (class "Default")
      (node (ref "MECH_S0B") (pin "28") (pinfunction "28_28") (pintype "bidirectional"))
    )
    (net (code "237") (name "unconnected-(MECH_S0B-Pad29)") (class "Default")
      (node (ref "MECH_S0B") (pin "29") (pinfunction "29_29") (pintype "bidirectional"))
    )
    (net (code "238") (name "unconnected-(MECH_S0B-Pad30)") (class "Default")
      (node (ref "MECH_S0B") (pin "30") (pinfunction "30_30") (pintype "bidirectional"))
    )
    (net (code "239") (name "unconnected-(MECH_S0B-Pad31)") (class "Default")
      (node (ref "MECH_S0B") (pin "31") (pinfunction "31_31") (pintype "bidirectional"))
    )
    (net (code "240") (name "unconnected-(MECH_S0B-Pad32)") (class "Default")
      (node (ref "MECH_S0B") (pin "32") (pinfunction "32_32") (pintype "bidirectional"))
    )
    (net (code "241") (name "unconnected-(MECH_S0B-Pad33)") (class "Default")
      (node (ref "MECH_S0B") (pin "33") (pinfunction "33_33") (pintype "bidirectional"))
    )
    (net (code "242") (name "unconnected-(MECH_S0B-Pad34)") (class "Default")
      (node (ref "MECH_S0B") (pin "34") (pinfunction "34_34") (pintype "bidirectional"))
    )
    (net (code "243") (name "unconnected-(MECH_S0B-Pad35)") (class "Default")
      (node (ref "MECH_S0B") (pin "35") (pinfunction "35_35") (pintype "bidirectional"))
    )
    (net (code "244") (name "unconnected-(MECH_S0B-Pad36)") (class "Default")
      (node (ref "MECH_S0B") (pin "36") (pinfunction "36_36") (pintype "bidirectional"))
    )
    (net (code "245") (name "unconnected-(MECH_S0B-Pad37)") (class "Default")
      (node (ref "MECH_S0B") (pin "37") (pinfunction "37_37") (pintype "bidirectional"))
    )
    (net (code "246") (name "unconnected-(MECH_S0B-Pad38)") (class "Default")
      (node (ref "MECH_S0B") (pin "38") (pinfunction "38_38") (pintype "bidirectional"))
    )
    (net (code "247") (name "unconnected-(MECH_S0B-Pad39)") (class "Default")
      (node (ref "MECH_S0B") (pin "39") (pinfunction "39_39") (pintype "bidirectional"))
    )
    (net (code "248") (name "unconnected-(MECH_S0B-Pad40)") (class "Default")
      (node (ref "MECH_S0B") (pin "40") (pinfunction "40_40") (pintype "bidirectional"))
    )
    (net (code "249") (name "unconnected-(MECH_S0B-Pad41)") (class "Default")
      (node (ref "MECH_S0B") (pin "41") (pinfunction "41_41") (pintype "bidirectional"))
    )
    (net (code "250") (name "unconnected-(MECH_S0B-Pad42)") (class "Default")
      (node (ref "MECH_S0B") (pin "42") (pinfunction "42_42") (pintype "bidirectional"))
    )
    (net (code "251") (name "unconnected-(MECH_S0B-Pad43)") (class "Default")
      (node (ref "MECH_S0B") (pin "43") (pinfunction "43_43") (pintype "bidirectional"))
    )
    (net (code "252") (name "unconnected-(MECH_S0B-Pad44)") (class "Default")
      (node (ref "MECH_S0B") (pin "44") (pinfunction "44_44") (pintype "bidirectional"))
    )
    (net (code "253") (name "unconnected-(MECH_S0B-Pad45)") (class "Default")
      (node (ref "MECH_S0B") (pin "45") (pinfunction "45_45") (pintype "bidirectional"))
    )
    (net (code "254") (name "unconnected-(MECH_S0B-Pad46)") (class "Default")
      (node (ref "MECH_S0B") (pin "46") (pinfunction "46_46") (pintype "bidirectional"))
    )
    (net (code "255") (name "unconnected-(MECH_S0B-Pad47)") (class "Default")
      (node (ref "MECH_S0B") (pin "47") (pinfunction "47_47") (pintype "bidirectional"))
    )
    (net (code "256") (name "unconnected-(MECH_S0B-Pad48)") (class "Default")
      (node (ref "MECH_S0B") (pin "48") (pinfunction "48_48") (pintype "bidirectional"))
    )
    (net (code "257") (name "unconnected-(MECH_S0B-Pad49)") (class "Default")
      (node (ref "MECH_S0B") (pin "49") (pinfunction "49_49") (pintype "bidirectional"))
    )
    (net (code "258") (name "unconnected-(MECH_S0B-Pad50)") (class "Default")
      (node (ref "MECH_S0B") (pin "50") (pinfunction "50_50") (pintype "bidirectional"))
    )
    (net (code "259") (name "unconnected-(MECH_S0B-Pad51)") (class "Default")
      (node (ref "MECH_S0B") (pin "51") (pinfunction "51_51") (pintype "bidirectional"))
    )
    (net (code "260") (name "unconnected-(MECH_S0B-Pad52)") (class "Default")
      (node (ref "MECH_S0B") (pin "52") (pinfunction "52_52") (pintype "bidirectional"))
    )
    (net (code "261") (name "unconnected-(MECH_S0B-Pad53)") (class "Default")
      (node (ref "MECH_S0B") (pin "53") (pinfunction "53_53") (pintype "bidirectional"))
    )
    (net (code "262") (name "unconnected-(MECH_S0B-Pad54)") (class "Default")
      (node (ref "MECH_S0B") (pin "54") (pinfunction "54_54") (pintype "bidirectional"))
    )
    (net (code "263") (name "unconnected-(MECH_S0B-Pad55)") (class "Default")
      (node (ref "MECH_S0B") (pin "55") (pinfunction "55_55") (pintype "bidirectional"))
    )
    (net (code "264") (name "unconnected-(MECH_S0B-Pad56)") (class "Default")
      (node (ref "MECH_S0B") (pin "56") (pinfunction "56_56") (pintype "bidirectional"))
    )
    (net (code "265") (name "unconnected-(MECH_S0B-Pad57)") (class "Default")
      (node (ref "MECH_S0B") (pin "57") (pinfunction "57_57") (pintype "bidirectional"))
    )
    (net (code "266") (name "unconnected-(MECH_S0B-Pad58)") (class "Default")
      (node (ref "MECH_S0B") (pin "58") (pinfunction "58_58") (pintype "bidirectional"))
    )
    (net (code "267") (name "unconnected-(MECH_S0B-Pad59)") (class "Default")
      (node (ref "MECH_S0B") (pin "59") (pinfunction "59_59") (pintype "bidirectional"))
    )
    (net (code "268") (name "unconnected-(MECH_S0B-Pad60)") (class "Default")
      (node (ref "MECH_S0B") (pin "60") (pinfunction "60_60") (pintype "bidirectional"))
    )
    (net (code "269") (name "unconnected-(MECH_S0B-Pad61)") (class "Default")
      (node (ref "MECH_S0B") (pin "61") (pinfunction "61_61") (pintype "bidirectional"))
    )
    (net (code "270") (name "unconnected-(MECH_S0B-Pad62)") (class "Default")
      (node (ref "MECH_S0B") (pin "62") (pinfunction "62_62") (pintype "bidirectional"))
    )
    (net (code "271") (name "unconnected-(MECH_S0B-Pad63)") (class "Default")
      (node (ref "MECH_S0B") (pin "63") (pinfunction "63_63") (pintype "bidirectional"))
    )
    (net (code "272") (name "unconnected-(MECH_S0B-Pad64)") (class "Default")
      (node (ref "MECH_S0B") (pin "64") (pinfunction "64_64") (pintype "bidirectional"))
    )
    (net (code "273") (name "unconnected-(MECH_S0B-Pad65)") (class "Default")
      (node (ref "MECH_S0B") (pin "65") (pinfunction "65_65") (pintype "bidirectional"))
    )
    (net (code "274") (name "unconnected-(MECH_S0B-Pad66)") (class "Default")
      (node (ref "MECH_S0B") (pin "66") (pinfunction "66_66") (pintype "bidirectional"))
    )
    (net (code "275") (name "unconnected-(MECH_S0B-Pad67)") (class "Default")
      (node (ref "MECH_S0B") (pin "67") (pinfunction "67_67") (pintype "bidirectional"))
    )
    (net (code "276") (name "unconnected-(MECH_S0B-Pad68)") (class "Default")
      (node (ref "MECH_S0B") (pin "68") (pinfunction "68_68") (pintype "bidirectional"))
    )
    (net (code "277") (name "unconnected-(MECH_S0B-Pad69)") (class "Default")
      (node (ref "MECH_S0B") (pin "69") (pinfunction "69_69") (pintype "bidirectional"))
    )
    (net (code "278") (name "unconnected-(MECH_S0B-Pad70)") (class "Default")
      (node (ref "MECH_S0B") (pin "70") (pinfunction "70_70") (pintype "bidirectional"))
    )
    (net (code "279") (name "unconnected-(MECH_W0B-Pad1)") (class "Default")
      (node (ref "MECH_W0B") (pin "1") (pinfunction "1_1") (pintype "bidirectional"))
    )
    (net (code "280") (name "unconnected-(MECH_W0B-Pad2)") (class "Default")
      (node (ref "MECH_W0B") (pin "2") (pinfunction "2_2") (pintype "bidirectional"))
    )
    (net (code "281") (name "unconnected-(MECH_W0B-Pad3)") (class "Default")
      (node (ref "MECH_W0B") (pin "3") (pinfunction "3_3") (pintype "bidirectional"))
    )
    (net (code "282") (name "unconnected-(MECH_W0B-Pad4)") (class "Default")
      (node (ref "MECH_W0B") (pin "4") (pinfunction "4_4") (pintype "bidirectional"))
    )
    (net (code "283") (name "unconnected-(MECH_W0B-Pad5)") (class "Default")
      (node (ref "MECH_W0B") (pin "5") (pinfunction "5_5") (pintype "bidirectional"))
    )
    (net (code "284") (name "unconnected-(MECH_W0B-Pad6)") (class "Default")
      (node (ref "MECH_W0B") (pin "6") (pinfunction "6_6") (pintype "bidirectional"))
    )
    (net (code "285") (name "unconnected-(MECH_W0B-Pad7)") (class "Default")
      (node (ref "MECH_W0B") (pin "7") (pinfunction "7_7") (pintype "bidirectional"))
    )
    (net (code "286") (name "unconnected-(MECH_W0B-Pad8)") (class "Default")
      (node (ref "MECH_W0B") (pin "8") (pinfunction "8_8") (pintype "bidirectional"))
    )
    (net (code "287") (name "unconnected-(MECH_W0B-Pad9)") (class "Default")
      (node (ref "MECH_W0B") (pin "9") (pinfunction "9_9") (pintype "bidirectional"))
    )
    (net (code "288") (name "unconnected-(MECH_W0B-Pad10)") (class "Default")
      (node (ref "MECH_W0B") (pin "10") (pinfunction "10_10") (pintype "bidirectional"))
    )
    (net (code "289") (name "unconnected-(MECH_W0B-Pad11)") (class "Default")
      (node (ref "MECH_W0B") (pin "11") (pinfunction "11_11") (pintype "bidirectional"))
    )
    (net (code "290") (name "unconnected-(MECH_W0B-Pad12)") (class "Default")
      (node (ref "MECH_W0B") (pin "12") (pinfunction "12_12") (pintype "bidirectional"))
    )
    (net (code "291") (name "unconnected-(MECH_W0B-Pad13)") (class "Default")
      (node (ref "MECH_W0B") (pin "13") (pinfunction "13_13") (pintype "bidirectional"))
    )
    (net (code "292") (name "unconnected-(MECH_W0B-Pad14)") (class "Default")
      (node (ref "MECH_W0B") (pin "14") (pinfunction "14_14") (pintype "bidirectional"))
    )
    (net (code "293") (name "unconnected-(MECH_W0B-Pad15)") (class "Default")
      (node (ref "MECH_W0B") (pin "15") (pinfunction "15_15") (pintype "bidirectional"))
    )
    (net (code "294") (name "unconnected-(MECH_W0B-Pad16)") (class "Default")
      (node (ref "MECH_W0B") (pin "16") (pinfunction "16_16") (pintype "bidirectional"))
    )
    (net (code "295") (name "unconnected-(MECH_W0B-Pad17)") (class "Default")
      (node (ref "MECH_W0B") (pin "17") (pinfunction "17_17") (pintype "bidirectional"))
    )
    (net (code "296") (name "unconnected-(MECH_W0B-Pad18)") (class "Default")
      (node (ref "MECH_W0B") (pin "18") (pinfunction "18_18") (pintype "bidirectional"))
    )
    (net (code "297") (name "unconnected-(MECH_W0B-Pad19)") (class "Default")
      (node (ref "MECH_W0B") (pin "19") (pinfunction "19_19") (pintype "bidirectional"))
    )
    (net (code "298") (name "unconnected-(MECH_W0B-Pad20)") (class "Default")
      (node (ref "MECH_W0B") (pin "20") (pinfunction "20_20") (pintype "bidirectional"))
    )
    (net (code "299") (name "unconnected-(MECH_W0B-Pad21)") (class "Default")
      (node (ref "MECH_W0B") (pin "21") (pinfunction "21_21") (pintype "bidirectional"))
    )
    (net (code "300") (name "unconnected-(MECH_W0B-Pad22)") (class "Default")
      (node (ref "MECH_W0B") (pin "22") (pinfunction "22_22") (pintype "bidirectional"))
    )
    (net (code "301") (name "unconnected-(MECH_W0B-Pad23)") (class "Default")
      (node (ref "MECH_W0B") (pin "23") (pinfunction "23_23") (pintype "bidirectional"))
    )
    (net (code "302") (name "unconnected-(MECH_W0B-Pad24)") (class "Default")
      (node (ref "MECH_W0B") (pin "24") (pinfunction "24_24") (pintype "bidirectional"))
    )
    (net (code "303") (name "unconnected-(MECH_W0B-Pad25)") (class "Default")
      (node (ref "MECH_W0B") (pin "25") (pinfunction "25_25") (pintype "bidirectional"))
    )
    (net (code "304") (name "unconnected-(MECH_W0B-Pad26)") (class "Default")
      (node (ref "MECH_W0B") (pin "26") (pinfunction "26_26") (pintype "bidirectional"))
    )
    (net (code "305") (name "unconnected-(MECH_W0B-Pad27)") (class "Default")
      (node (ref "MECH_W0B") (pin "27") (pinfunction "27_27") (pintype "bidirectional"))
    )
    (net (code "306") (name "unconnected-(MECH_W0B-Pad28)") (class "Default")
      (node (ref "MECH_W0B") (pin "28") (pinfunction "28_28") (pintype "bidirectional"))
    )
    (net (code "307") (name "unconnected-(MECH_W0B-Pad29)") (class "Default")
      (node (ref "MECH_W0B") (pin "29") (pinfunction "29_29") (pintype "bidirectional"))
    )
    (net (code "308") (name "unconnected-(MECH_W0B-Pad30)") (class "Default")
      (node (ref "MECH_W0B") (pin "30") (pinfunction "30_30") (pintype "bidirectional"))
    )
    (net (code "309") (name "unconnected-(MECH_W0B-Pad31)") (class "Default")
      (node (ref "MECH_W0B") (pin "31") (pinfunction "31_31") (pintype "bidirectional"))
    )
    (net (code "310") (name "unconnected-(MECH_W0B-Pad32)") (class "Default")
      (node (ref "MECH_W0B") (pin "32") (pinfunction "32_32") (pintype "bidirectional"))
    )
    (net (code "311") (name "unconnected-(MECH_W0B-Pad33)") (class "Default")
      (node (ref "MECH_W0B") (pin "33") (pinfunction "33_33") (pintype "bidirectional"))
    )
    (net (code "312") (name "unconnected-(MECH_W0B-Pad34)") (class "Default")
      (node (ref "MECH_W0B") (pin "34") (pinfunction "34_34") (pintype "bidirectional"))
    )
    (net (code "313") (name "unconnected-(MECH_W0B-Pad35)") (class "Default")
      (node (ref "MECH_W0B") (pin "35") (pinfunction "35_35") (pintype "bidirectional"))
    )
    (net (code "314") (name "unconnected-(MECH_W0B-Pad36)") (class "Default")
      (node (ref "MECH_W0B") (pin "36") (pinfunction "36_36") (pintype "bidirectional"))
    )
    (net (code "315") (name "unconnected-(MECH_W0B-Pad37)") (class "Default")
      (node (ref "MECH_W0B") (pin "37") (pinfunction "37_37") (pintype "bidirectional"))
    )
    (net (code "316") (name "unconnected-(MECH_W0B-Pad38)") (class "Default")
      (node (ref "MECH_W0B") (pin "38") (pinfunction "38_38") (pintype "bidirectional"))
    )
    (net (code "317") (name "unconnected-(MECH_W0B-Pad39)") (class "Default")
      (node (ref "MECH_W0B") (pin "39") (pinfunction "39_39") (pintype "bidirectional"))
    )
    (net (code "318") (name "unconnected-(MECH_W0B-Pad40)") (class "Default")
      (node (ref "MECH_W0B") (pin "40") (pinfunction "40_40") (pintype "bidirectional"))
    )
    (net (code "319") (name "unconnected-(MECH_W0B-Pad41)") (class "Default")
      (node (ref "MECH_W0B") (pin "41") (pinfunction "41_41") (pintype "bidirectional"))
    )
    (net (code "320") (name "unconnected-(MECH_W0B-Pad42)") (class "Default")
      (node (ref "MECH_W0B") (pin "42") (pinfunction "42_42") (pintype "bidirectional"))
    )
    (net (code "321") (name "unconnected-(MECH_W0B-Pad43)") (class "Default")
      (node (ref "MECH_W0B") (pin "43") (pinfunction "43_43") (pintype "bidirectional"))
    )
    (net (code "322") (name "unconnected-(MECH_W0B-Pad44)") (class "Default")
      (node (ref "MECH_W0B") (pin "44") (pinfunction "44_44") (pintype "bidirectional"))
    )
    (net (code "323") (name "unconnected-(MECH_W0B-Pad45)") (class "Default")
      (node (ref "MECH_W0B") (pin "45") (pinfunction "45_45") (pintype "bidirectional"))
    )
    (net (code "324") (name "unconnected-(MECH_W0B-Pad46)") (class "Default")
      (node (ref "MECH_W0B") (pin "46") (pinfunction "46_46") (pintype "bidirectional"))
    )
    (net (code "325") (name "unconnected-(MECH_W0B-Pad47)") (class "Default")
      (node (ref "MECH_W0B") (pin "47") (pinfunction "47_47") (pintype "bidirectional"))
    )
    (net (code "326") (name "unconnected-(MECH_W0B-Pad48)") (class "Default")
      (node (ref "MECH_W0B") (pin "48") (pinfunction "48_48") (pintype "bidirectional"))
    )
    (net (code "327") (name "unconnected-(MECH_W0B-Pad49)") (class "Default")
      (node (ref "MECH_W0B") (pin "49") (pinfunction "49_49") (pintype "bidirectional"))
    )
    (net (code "328") (name "unconnected-(MECH_W0B-Pad50)") (class "Default")
      (node (ref "MECH_W0B") (pin "50") (pinfunction "50_50") (pintype "bidirectional"))
    )
    (net (code "329") (name "unconnected-(MECH_W0B-Pad51)") (class "Default")
      (node (ref "MECH_W0B") (pin "51") (pinfunction "51_51") (pintype "bidirectional"))
    )
    (net (code "330") (name "unconnected-(MECH_W0B-Pad52)") (class "Default")
      (node (ref "MECH_W0B") (pin "52") (pinfunction "52_52") (pintype "bidirectional"))
    )
    (net (code "331") (name "unconnected-(MECH_W0B-Pad53)") (class "Default")
      (node (ref "MECH_W0B") (pin "53") (pinfunction "53_53") (pintype "bidirectional"))
    )
    (net (code "332") (name "unconnected-(MECH_W0B-Pad54)") (class "Default")
      (node (ref "MECH_W0B") (pin "54") (pinfunction "54_54") (pintype "bidirectional"))
    )
    (net (code "333") (name "unconnected-(MECH_W0B-Pad55)") (class "Default")
      (node (ref "MECH_W0B") (pin "55") (pinfunction "55_55") (pintype "bidirectional"))
    )
    (net (code "334") (name "unconnected-(MECH_W0B-Pad56)") (class "Default")
      (node (ref "MECH_W0B") (pin "56") (pinfunction "56_56") (pintype "bidirectional"))
    )
    (net (code "335") (name "unconnected-(MECH_W0B-Pad57)") (class "Default")
      (node (ref "MECH_W0B") (pin "57") (pinfunction "57_57") (pintype "bidirectional"))
    )
    (net (code "336") (name "unconnected-(MECH_W0B-Pad58)") (class "Default")
      (node (ref "MECH_W0B") (pin "58") (pinfunction "58_58") (pintype "bidirectional"))
    )
    (net (code "337") (name "unconnected-(MECH_W0B-Pad59)") (class "Default")
      (node (ref "MECH_W0B") (pin "59") (pinfunction "59_59") (pintype "bidirectional"))
    )
    (net (code "338") (name "unconnected-(MECH_W0B-Pad60)") (class "Default")
      (node (ref "MECH_W0B") (pin "60") (pinfunction "60_60") (pintype "bidirectional"))
    )
    (net (code "339") (name "unconnected-(MECH_W0B-Pad61)") (class "Default")
      (node (ref "MECH_W0B") (pin "61") (pinfunction "61_61") (pintype "bidirectional"))
    )
    (net (code "340") (name "unconnected-(MECH_W0B-Pad62)") (class "Default")
      (node (ref "MECH_W0B") (pin "62") (pinfunction "62_62") (pintype "bidirectional"))
    )
    (net (code "341") (name "unconnected-(MECH_W0B-Pad63)") (class "Default")
      (node (ref "MECH_W0B") (pin "63") (pinfunction "63_63") (pintype "bidirectional"))
    )
    (net (code "342") (name "unconnected-(MECH_W0B-Pad64)") (class "Default")
      (node (ref "MECH_W0B") (pin "64") (pinfunction "64_64") (pintype "bidirectional"))
    )
    (net (code "343") (name "unconnected-(MECH_W0B-Pad65)") (class "Default")
      (node (ref "MECH_W0B") (pin "65") (pinfunction "65_65") (pintype "bidirectional"))
    )
    (net (code "344") (name "unconnected-(MECH_W0B-Pad66)") (class "Default")
      (node (ref "MECH_W0B") (pin "66") (pinfunction "66_66") (pintype "bidirectional"))
    )
    (net (code "345") (name "unconnected-(MECH_W0B-Pad67)") (class "Default")
      (node (ref "MECH_W0B") (pin "67") (pinfunction "67_67") (pintype "bidirectional"))
    )
    (net (code "346") (name "unconnected-(MECH_W0B-Pad68)") (class "Default")
      (node (ref "MECH_W0B") (pin "68") (pinfunction "68_68") (pintype "bidirectional"))
    )
    (net (code "347") (name "unconnected-(MECH_W0B-Pad69)") (class "Default")
      (node (ref "MECH_W0B") (pin "69") (pinfunction "69_69") (pintype "bidirectional"))
    )
    (net (code "348") (name "unconnected-(MECH_W0B-Pad70)") (class "Default")
      (node (ref "MECH_W0B") (pin "70") (pinfunction "70_70") (pintype "bidirectional"))
    )
    (net (code "349") (name "unconnected-(U$2-Pad1)") (class "Default")
      (node (ref "U$2") (pin "1") (pinfunction "1_1") (pintype "bidirectional"))
    )
    (net (code "350") (name "unconnected-(U$2-Pad2)") (class "Default")
      (node (ref "U$2") (pin "2") (pinfunction "2_2") (pintype "bidirectional"))
    )
    (net (code "351") (name "unconnected-(U$2-Pad3)") (class "Default")
      (node (ref "U$2") (pin "3") (pinfunction "3_3") (pintype "bidirectional"))
    )
    (net (code "352") (name "unconnected-(U$2-Pad4)") (class "Default")
      (node (ref "U$2") (pin "4") (pinfunction "4_4") (pintype "bidirectional"))
    )
    (net (code "353") (name "unconnected-(U$2-Pad5)") (class "Default")
      (node (ref "U$2") (pin "5") (pinfunction "5_5") (pintype "bidirectional"))
    )
    (net (code "354") (name "unconnected-(U$2-Pad6)") (class "Default")
      (node (ref "U$2") (pin "6") (pinfunction "6_6") (pintype "bidirectional"))
    )
    (net (code "355") (name "unconnected-(U$2-Pad7)") (class "Default")
      (node (ref "U$2") (pin "7") (pinfunction "7_7") (pintype "bidirectional"))
    )
    (net (code "356") (name "unconnected-(U$2-Pad8)") (class "Default")
      (node (ref "U$2") (pin "8") (pinfunction "8_8") (pintype "bidirectional"))
    )
    (net (code "357") (name "unconnected-(U$2-Pad9)") (class "Default")
      (node (ref "U$2") (pin "9") (pinfunction "9_9") (pintype "bidirectional"))
    )
    (net (code "358") (name "unconnected-(U$2-Pad10)") (class "Default")
      (node (ref "U$2") (pin "10") (pinfunction "10_10") (pintype "bidirectional"))
    )
    (net (code "359") (name "unconnected-(U$2-Pad11)") (class "Default")
      (node (ref "U$2") (pin "11") (pinfunction "11_11") (pintype "bidirectional"))
    )
    (net (code "360") (name "unconnected-(U$2-Pad12)") (class "Default")
      (node (ref "U$2") (pin "12") (pinfunction "12_12") (pintype "bidirectional"))
    )
    (net (code "361") (name "unconnected-(U$2-Pad13)") (class "Default")
      (node (ref "U$2") (pin "13") (pinfunction "13_13") (pintype "bidirectional"))
    )
    (net (code "362") (name "unconnected-(U$2-Pad14)") (class "Default")
      (node (ref "U$2") (pin "14") (pinfunction "14_14") (pintype "bidirectional"))
    )
    (net (code "363") (name "unconnected-(U$2-Pad15)") (class "Default")
      (node (ref "U$2") (pin "15") (pinfunction "15_15") (pintype "bidirectional"))
    )
    (net (code "364") (name "unconnected-(U$2-Pad16)") (class "Default")
      (node (ref "U$2") (pin "16") (pinfunction "16_16") (pintype "bidirectional"))
    )
    (net (code "365") (name "unconnected-(U$2-Pad17)") (class "Default")
      (node (ref "U$2") (pin "17") (pinfunction "17_17") (pintype "bidirectional"))
    )
    (net (code "366") (name "unconnected-(U$2-Pad18)") (class "Default")
      (node (ref "U$2") (pin "18") (pinfunction "18_18") (pintype "bidirectional"))
    )
    (net (code "367") (name "unconnected-(U$2-Pad19)") (class "Default")
      (node (ref "U$2") (pin "19") (pinfunction "19_19") (pintype "bidirectional"))
    )
    (net (code "368") (name "unconnected-(U$2-Pad20)") (class "Default")
      (node (ref "U$2") (pin "20") (pinfunction "20_20") (pintype "bidirectional"))
    )
    (net (code "369") (name "unconnected-(U$6-A-Pad2)") (class "Default")
      (node (ref "U$6") (pin "2") (pinfunction "A_2") (pintype "input"))
    )
    (net (code "370") (name "unconnected-(U1-RES-Pad5)") (class "Default")
      (node (ref "U1") (pin "5") (pinfunction "RES_5") (pintype "passive"))
    )
    (net (code "371") (name "unconnected-(U2-RES-Pad5)") (class "Default")
      (node (ref "U2") (pin "5") (pinfunction "RES_5") (pintype "passive"))
    )
    (net (code "372") (name "unconnected-(U3-RES-Pad5)") (class "Default")
      (node (ref "U3") (pin "5") (pinfunction "RES_5") (pintype "passive"))
    )
    (net (code "373") (name "unconnected-(U4-PadNC1)") (class "Default")
      (node (ref "U4") (pin "NC1") (pinfunction "NC1_NC1") (pintype "bidirectional"))
    )
    (net (code "374") (name "unconnected-(U4-PadNC2)") (class "Default")
      (node (ref "U4") (pin "NC2") (pinfunction "NC2_NC2") (pintype "bidirectional"))
    )
    (net (code "375") (name "unconnected-(U4-PadNC3)") (class "Default")
      (node (ref "U4") (pin "NC3") (pinfunction "NC3_NC3") (pintype "bidirectional"))
    )
    (net (code "376") (name "unconnected-(U4-PadNC4)") (class "Default")
      (node (ref "U4") (pin "NC4") (pinfunction "NC4_NC4") (pintype "bidirectional"))
    )
    (net (code "377") (name "unconnected-(U4-PadNC5)") (class "Default")
      (node (ref "U4") (pin "NC5") (pinfunction "NC5_NC5") (pintype "bidirectional"))
    )
    (net (code "378") (name "unconnected-(U4-PadNC6)") (class "Default")
      (node (ref "U4") (pin "NC6") (pinfunction "NC6_NC6") (pintype "bidirectional"))
    )
  )
)
